# MicroMouse_v04.net
KiCad netlist of a schematic drawn in EasyEDA Pro
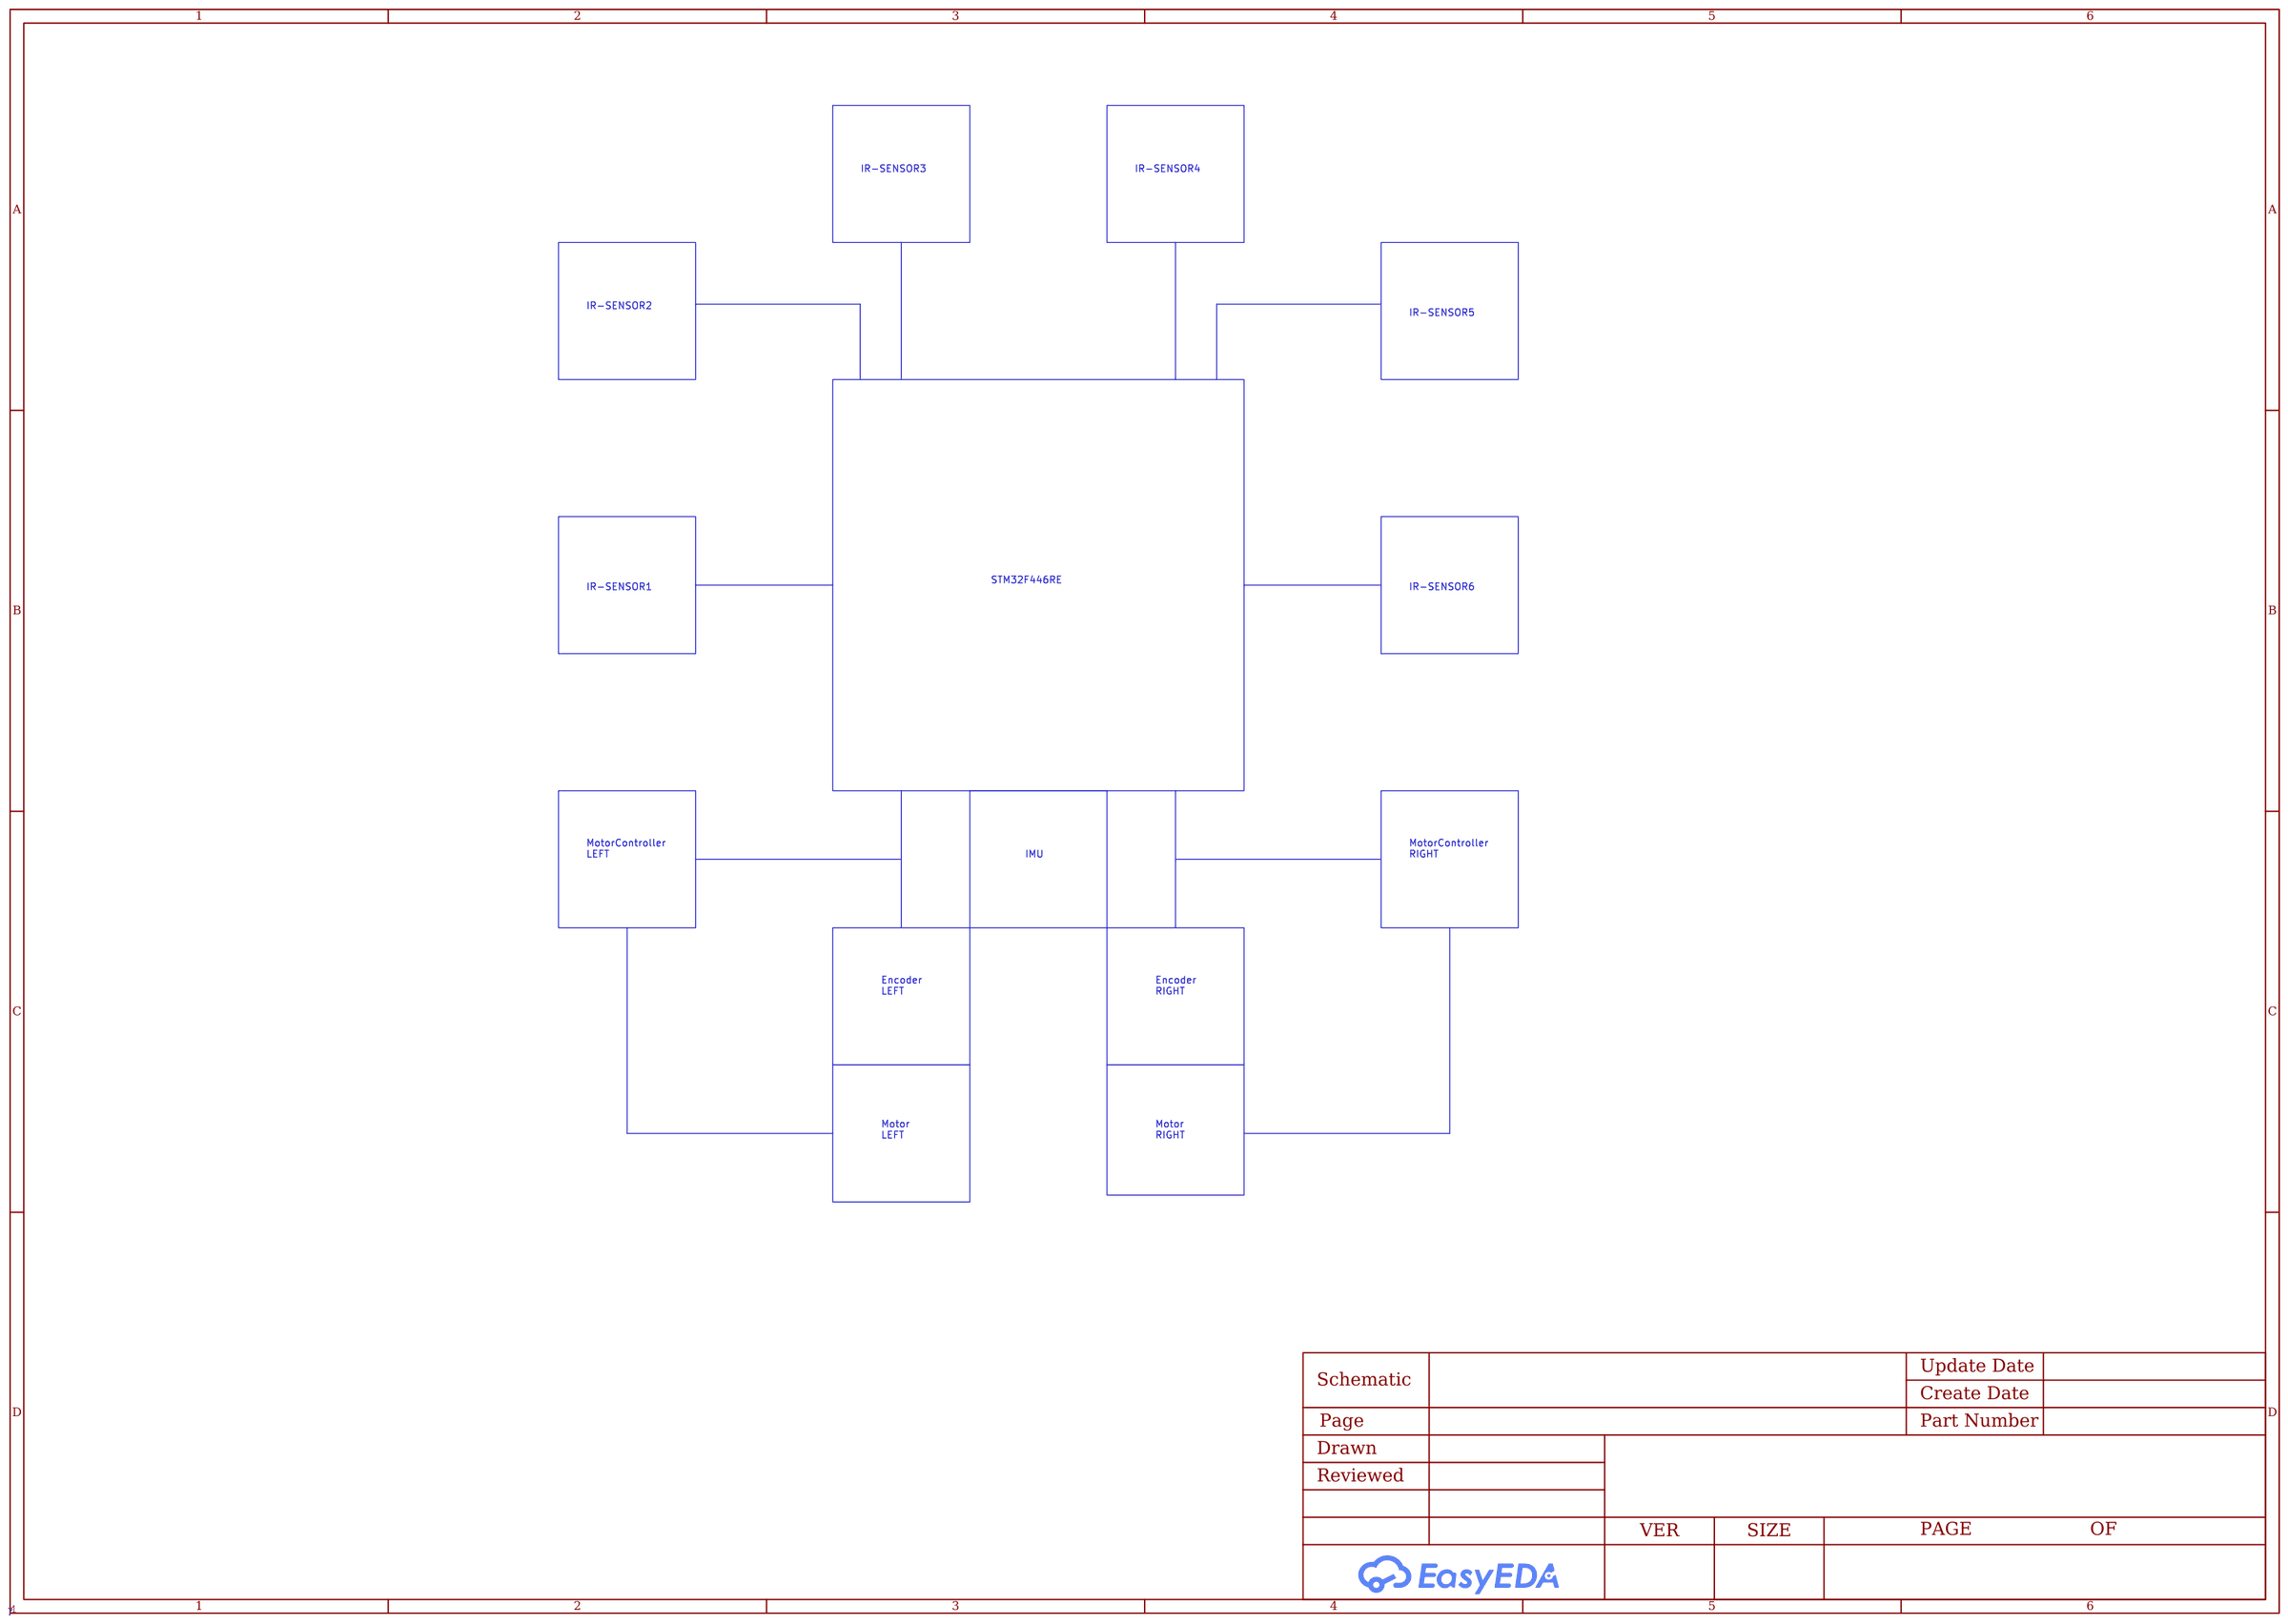
[diagram p0: Overview]
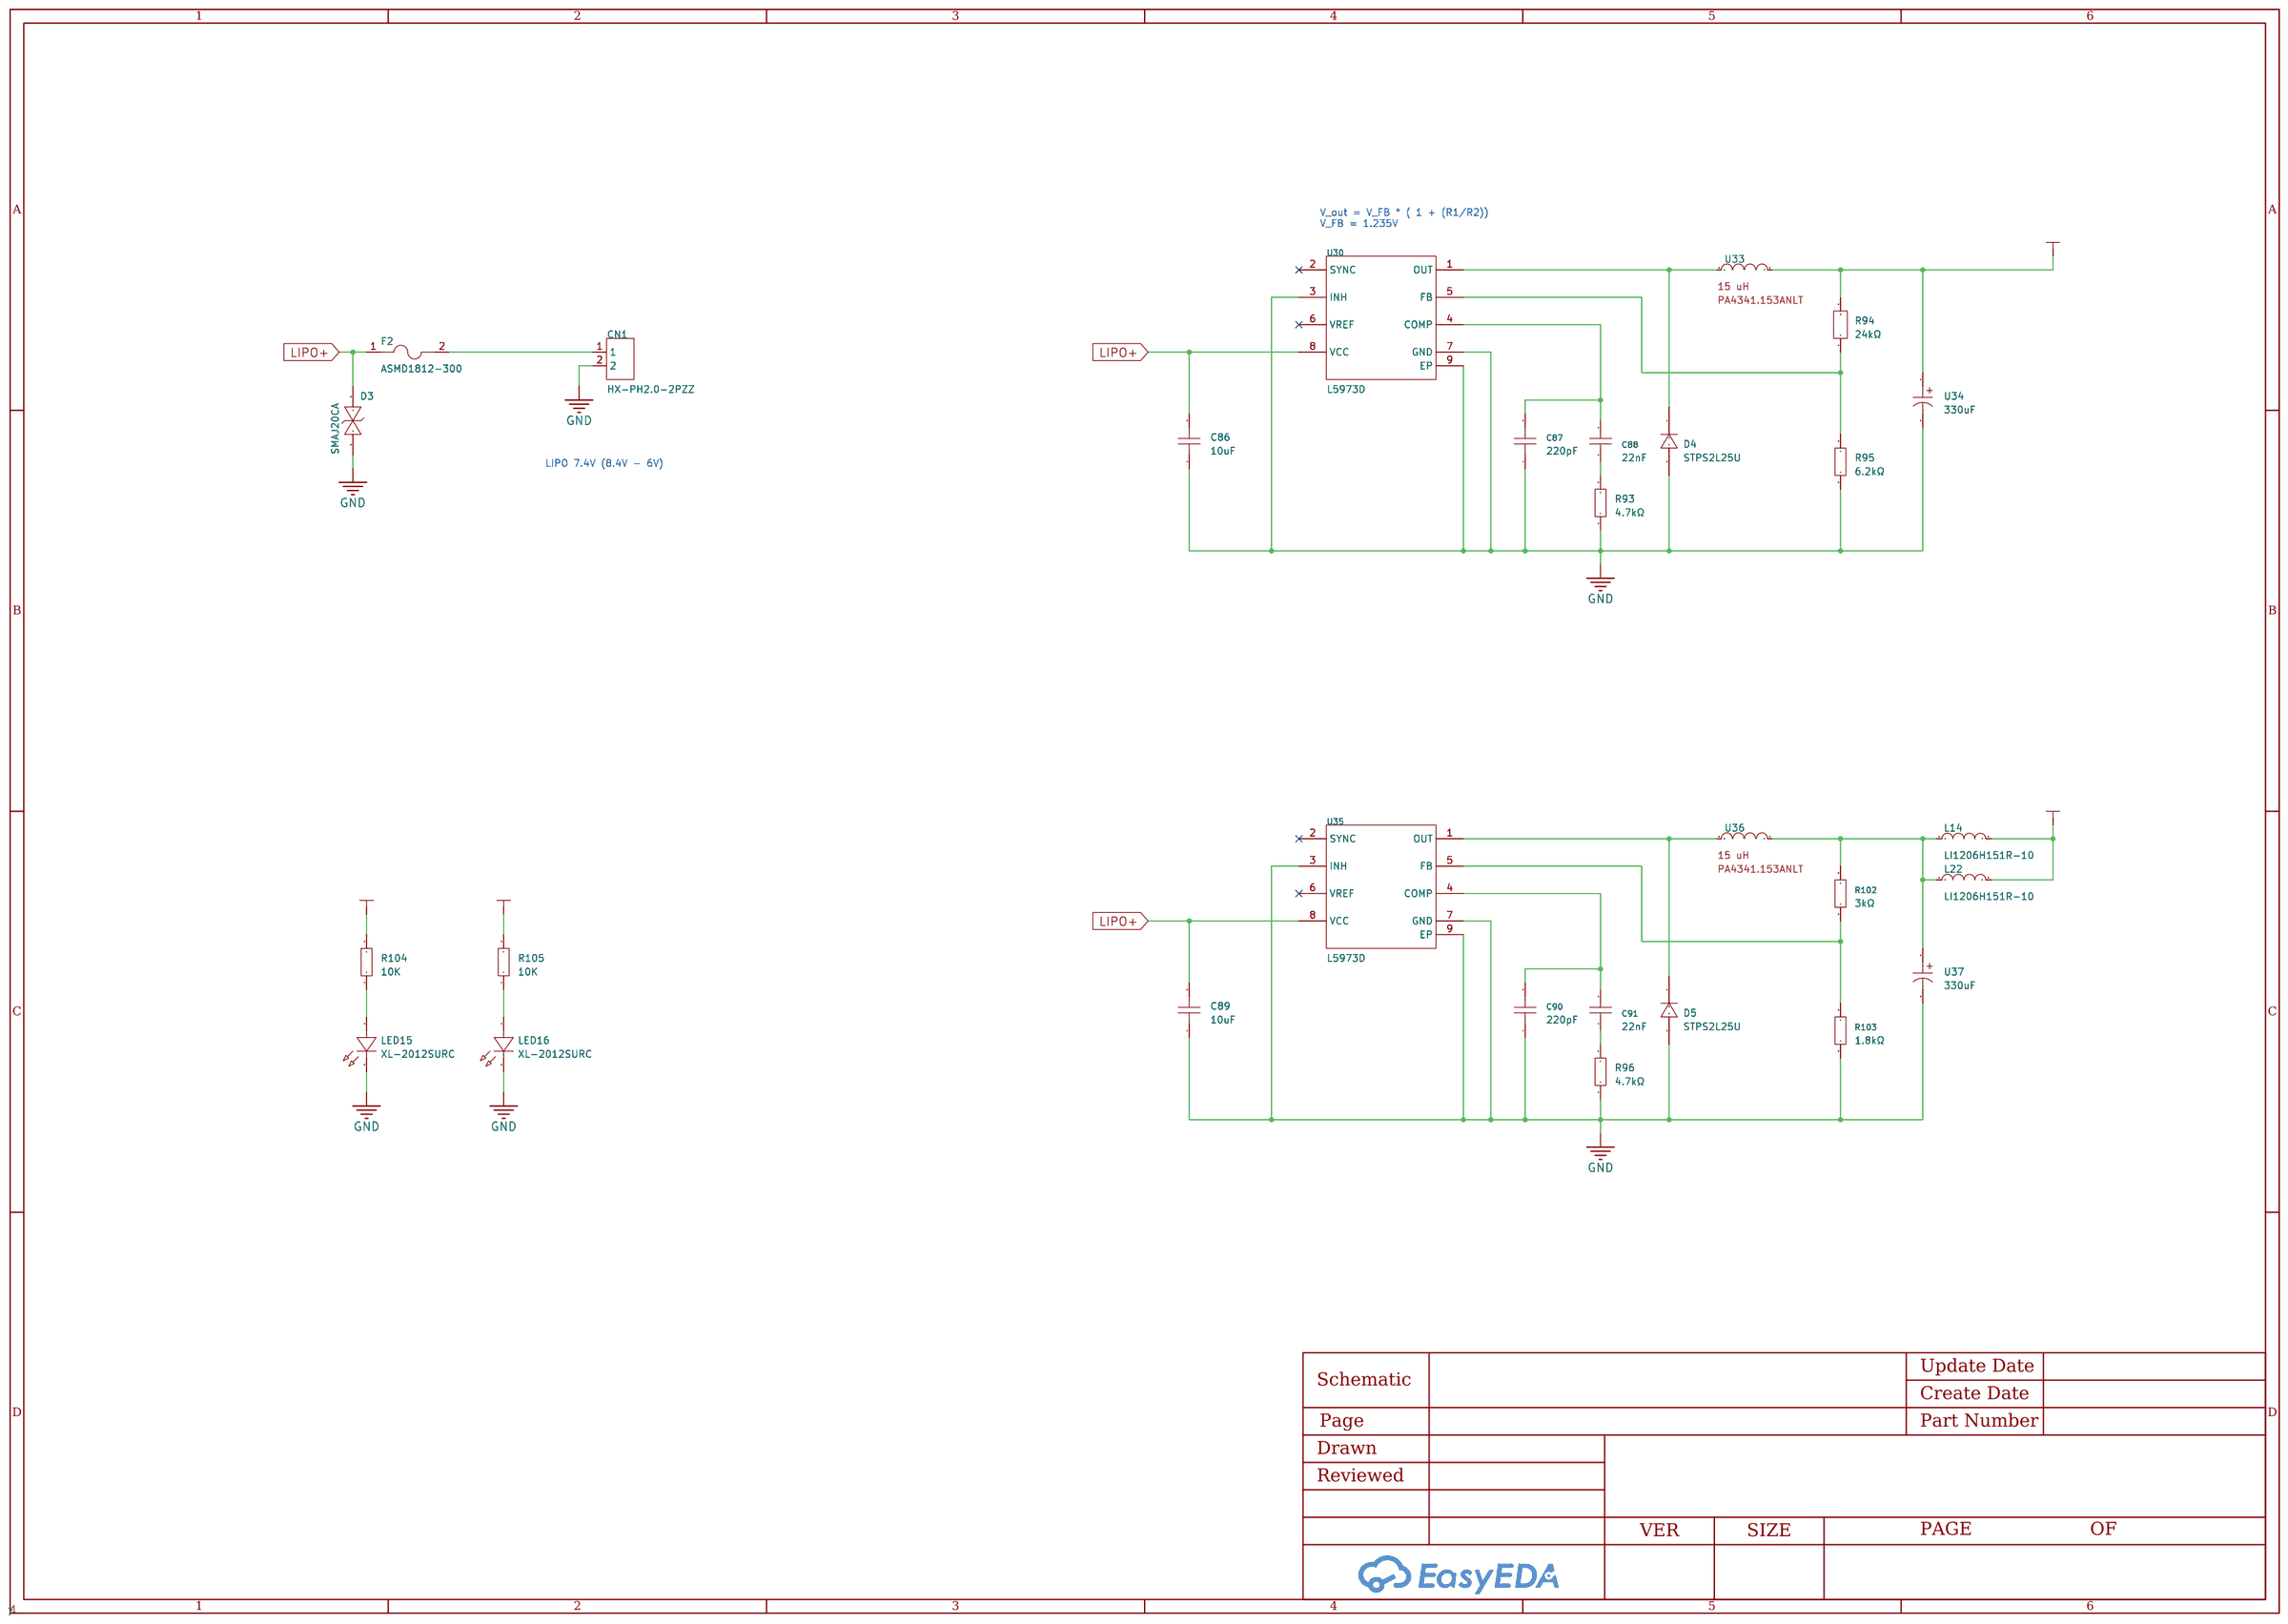
[diagram p1: VCC]
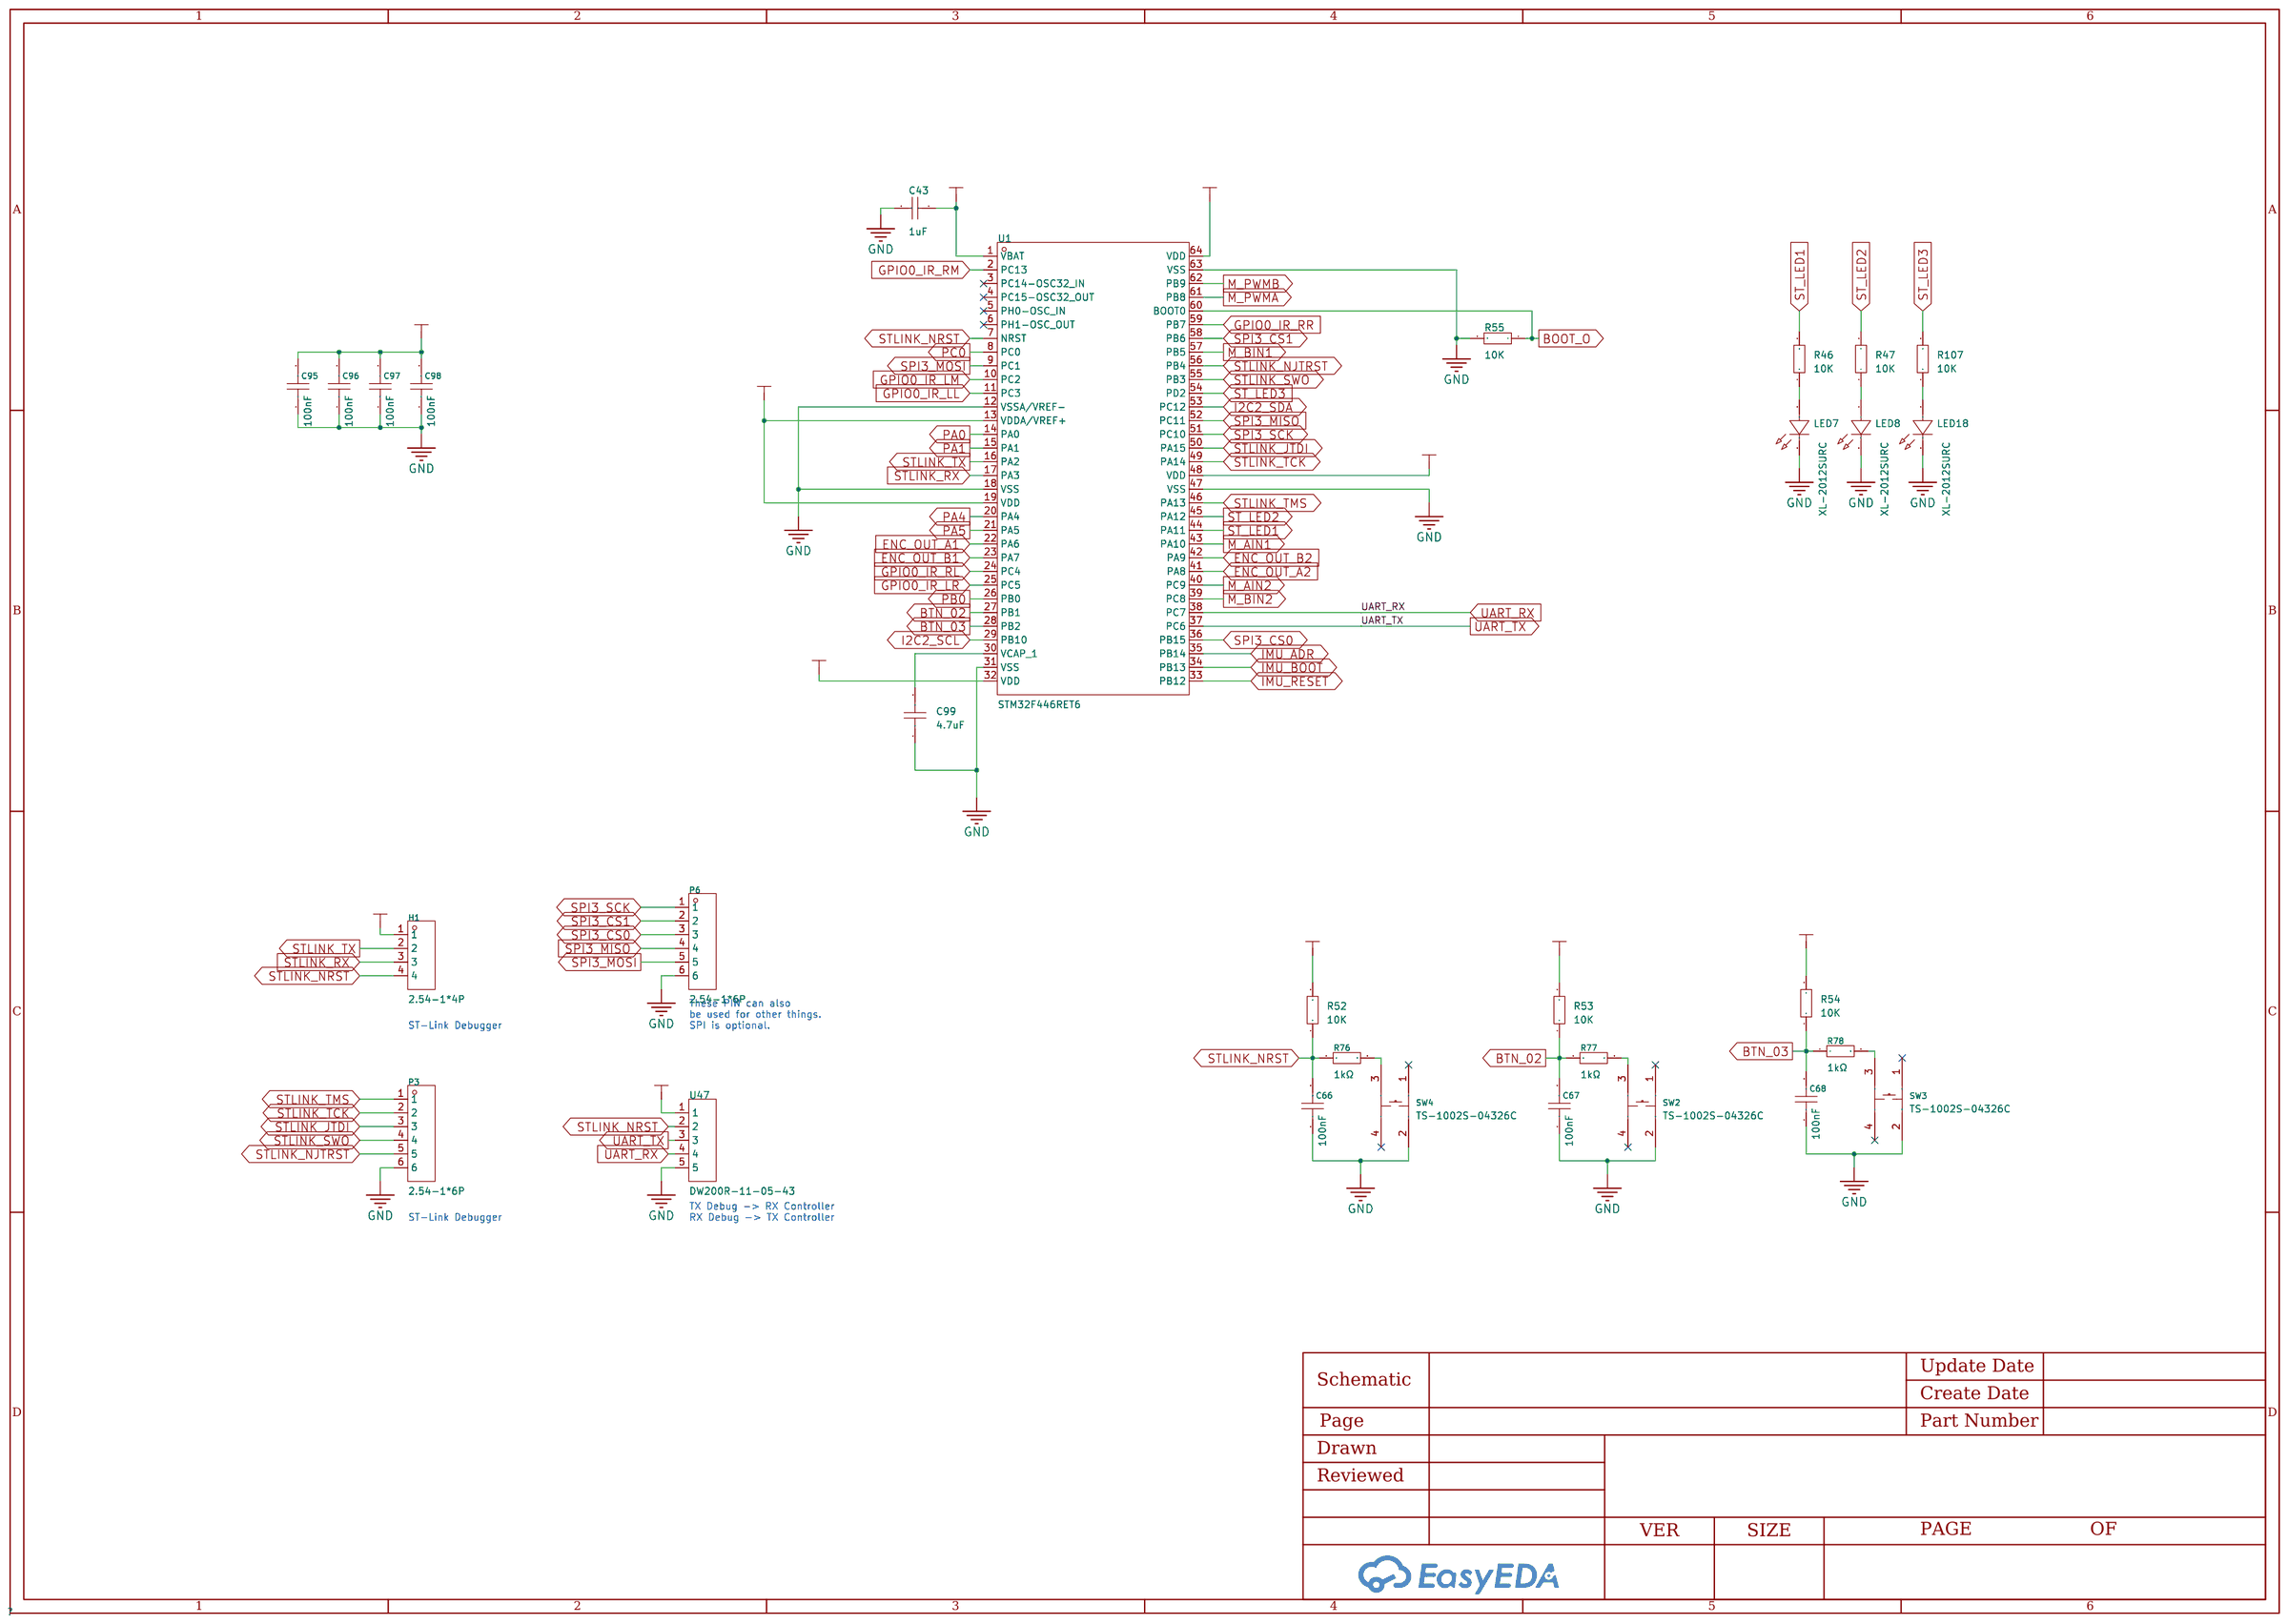
[diagram p2: Controller]
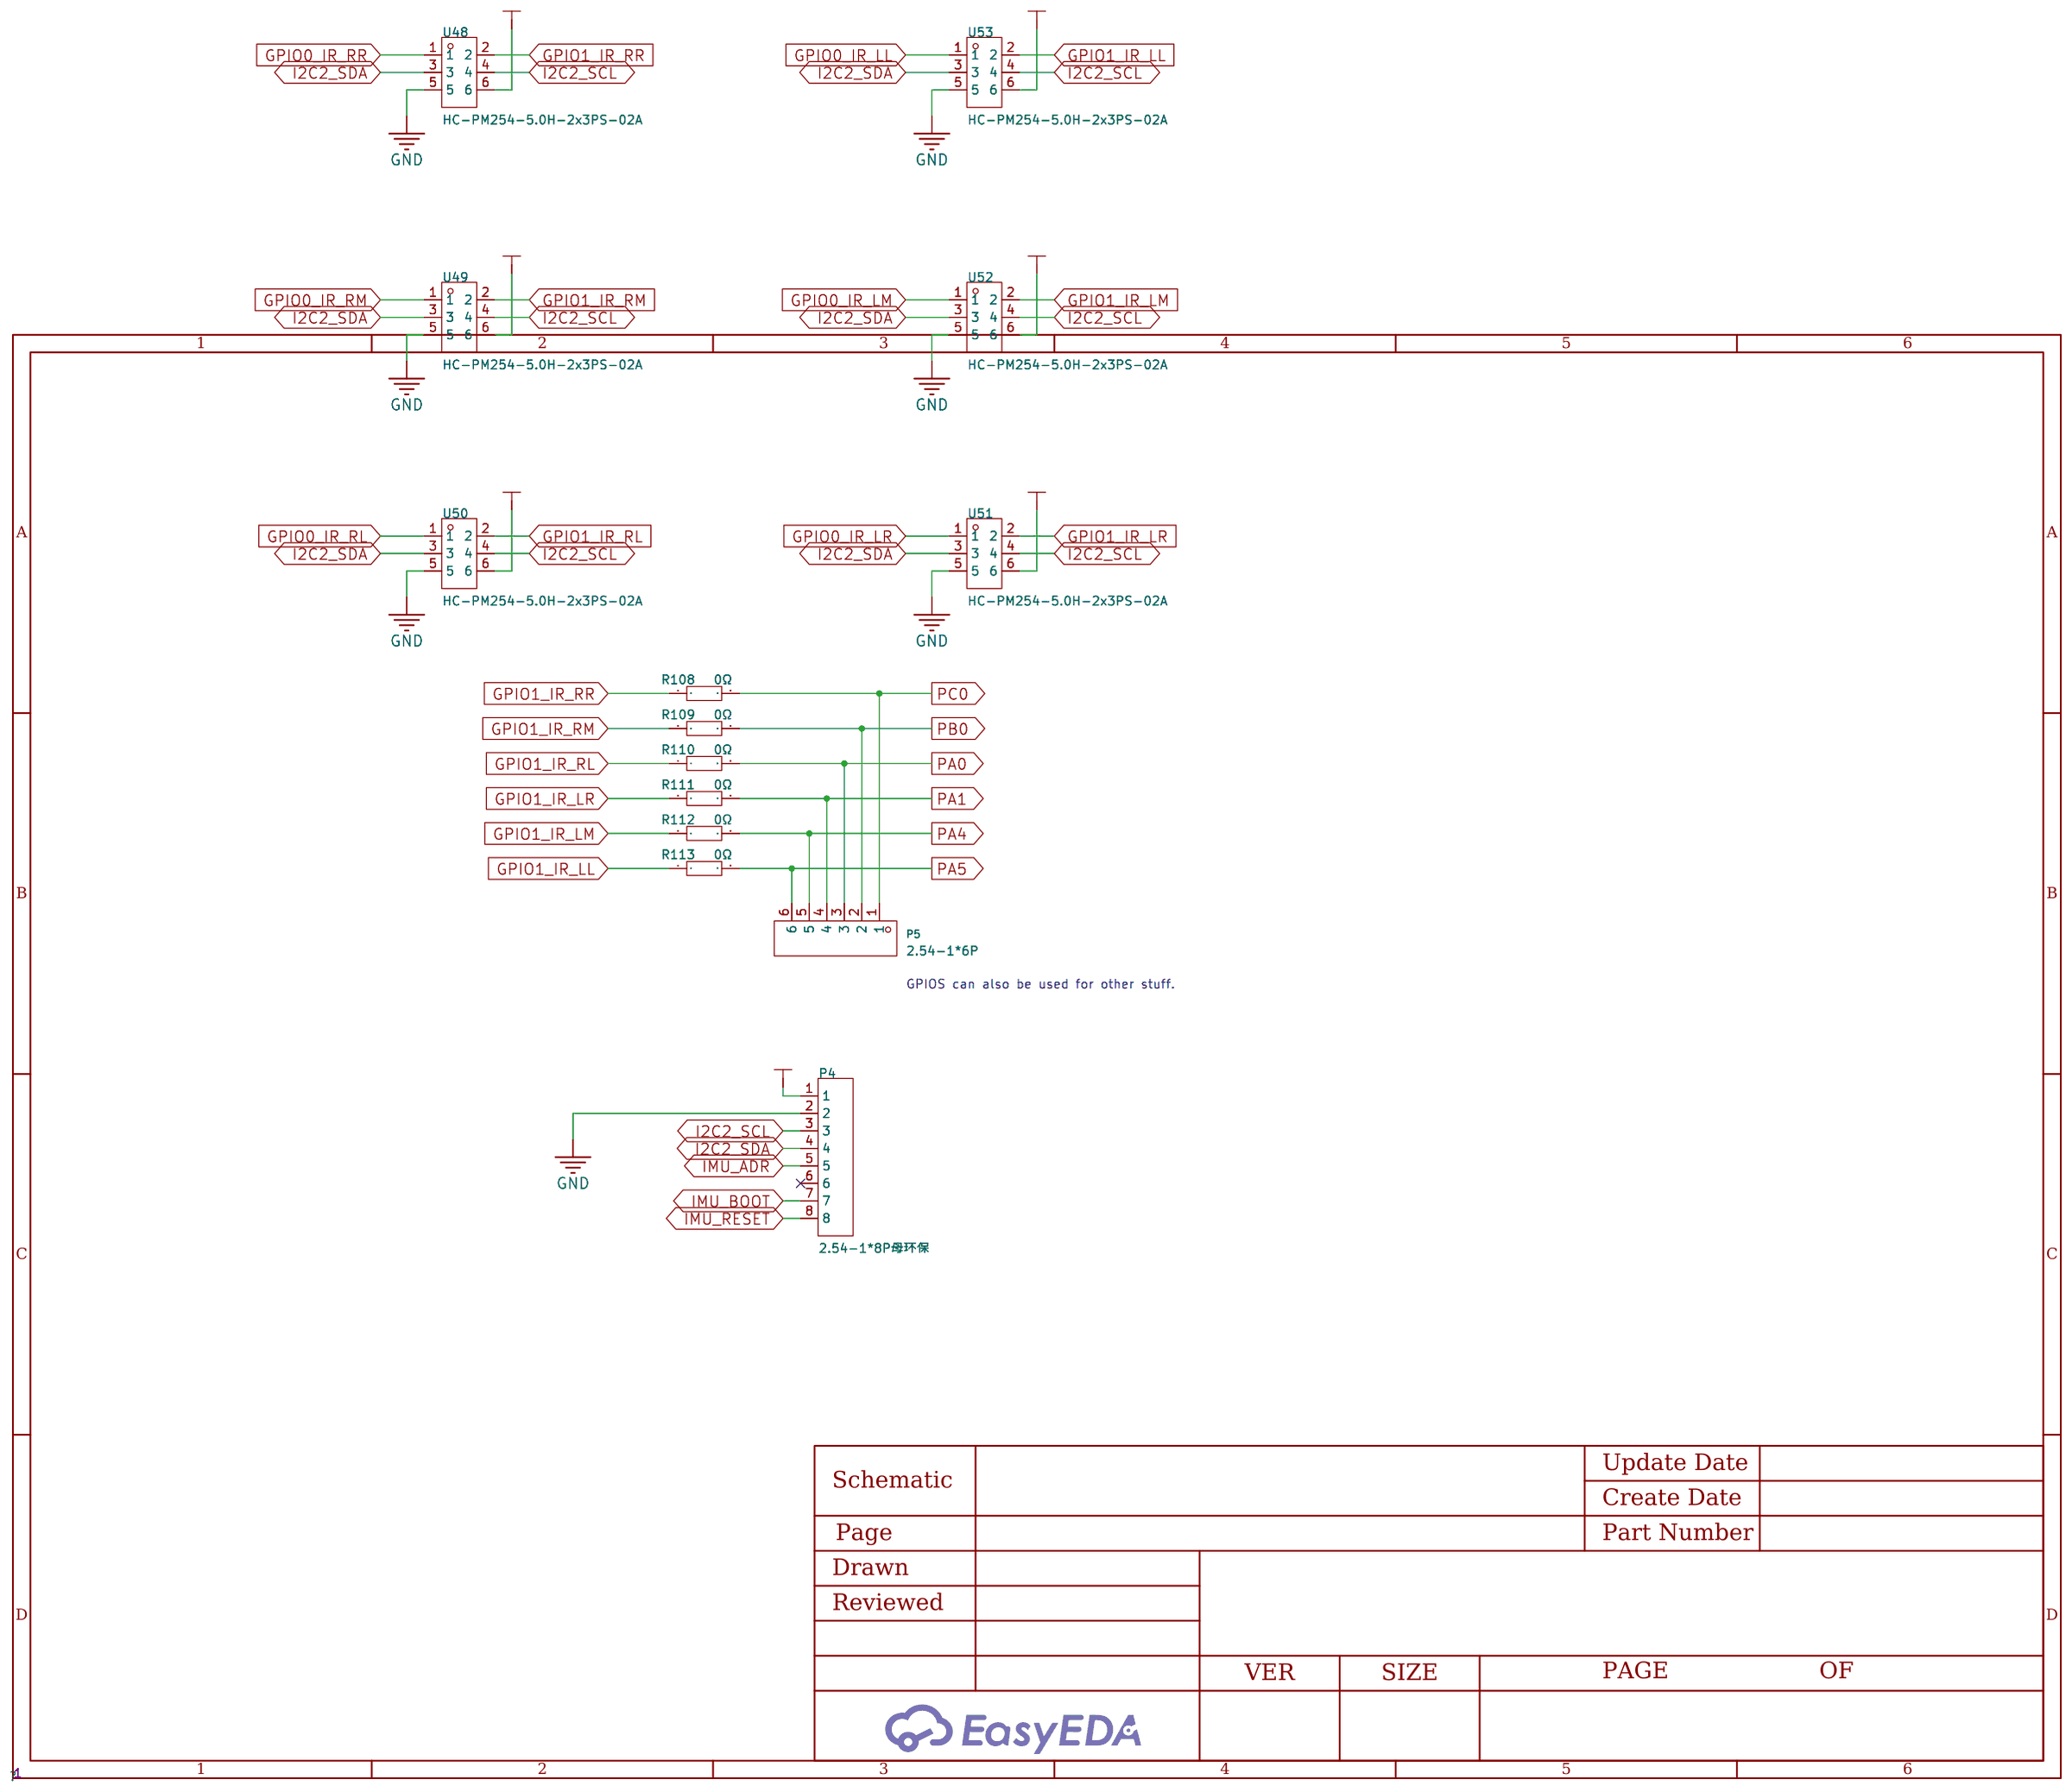
[diagram p3: Sensors]
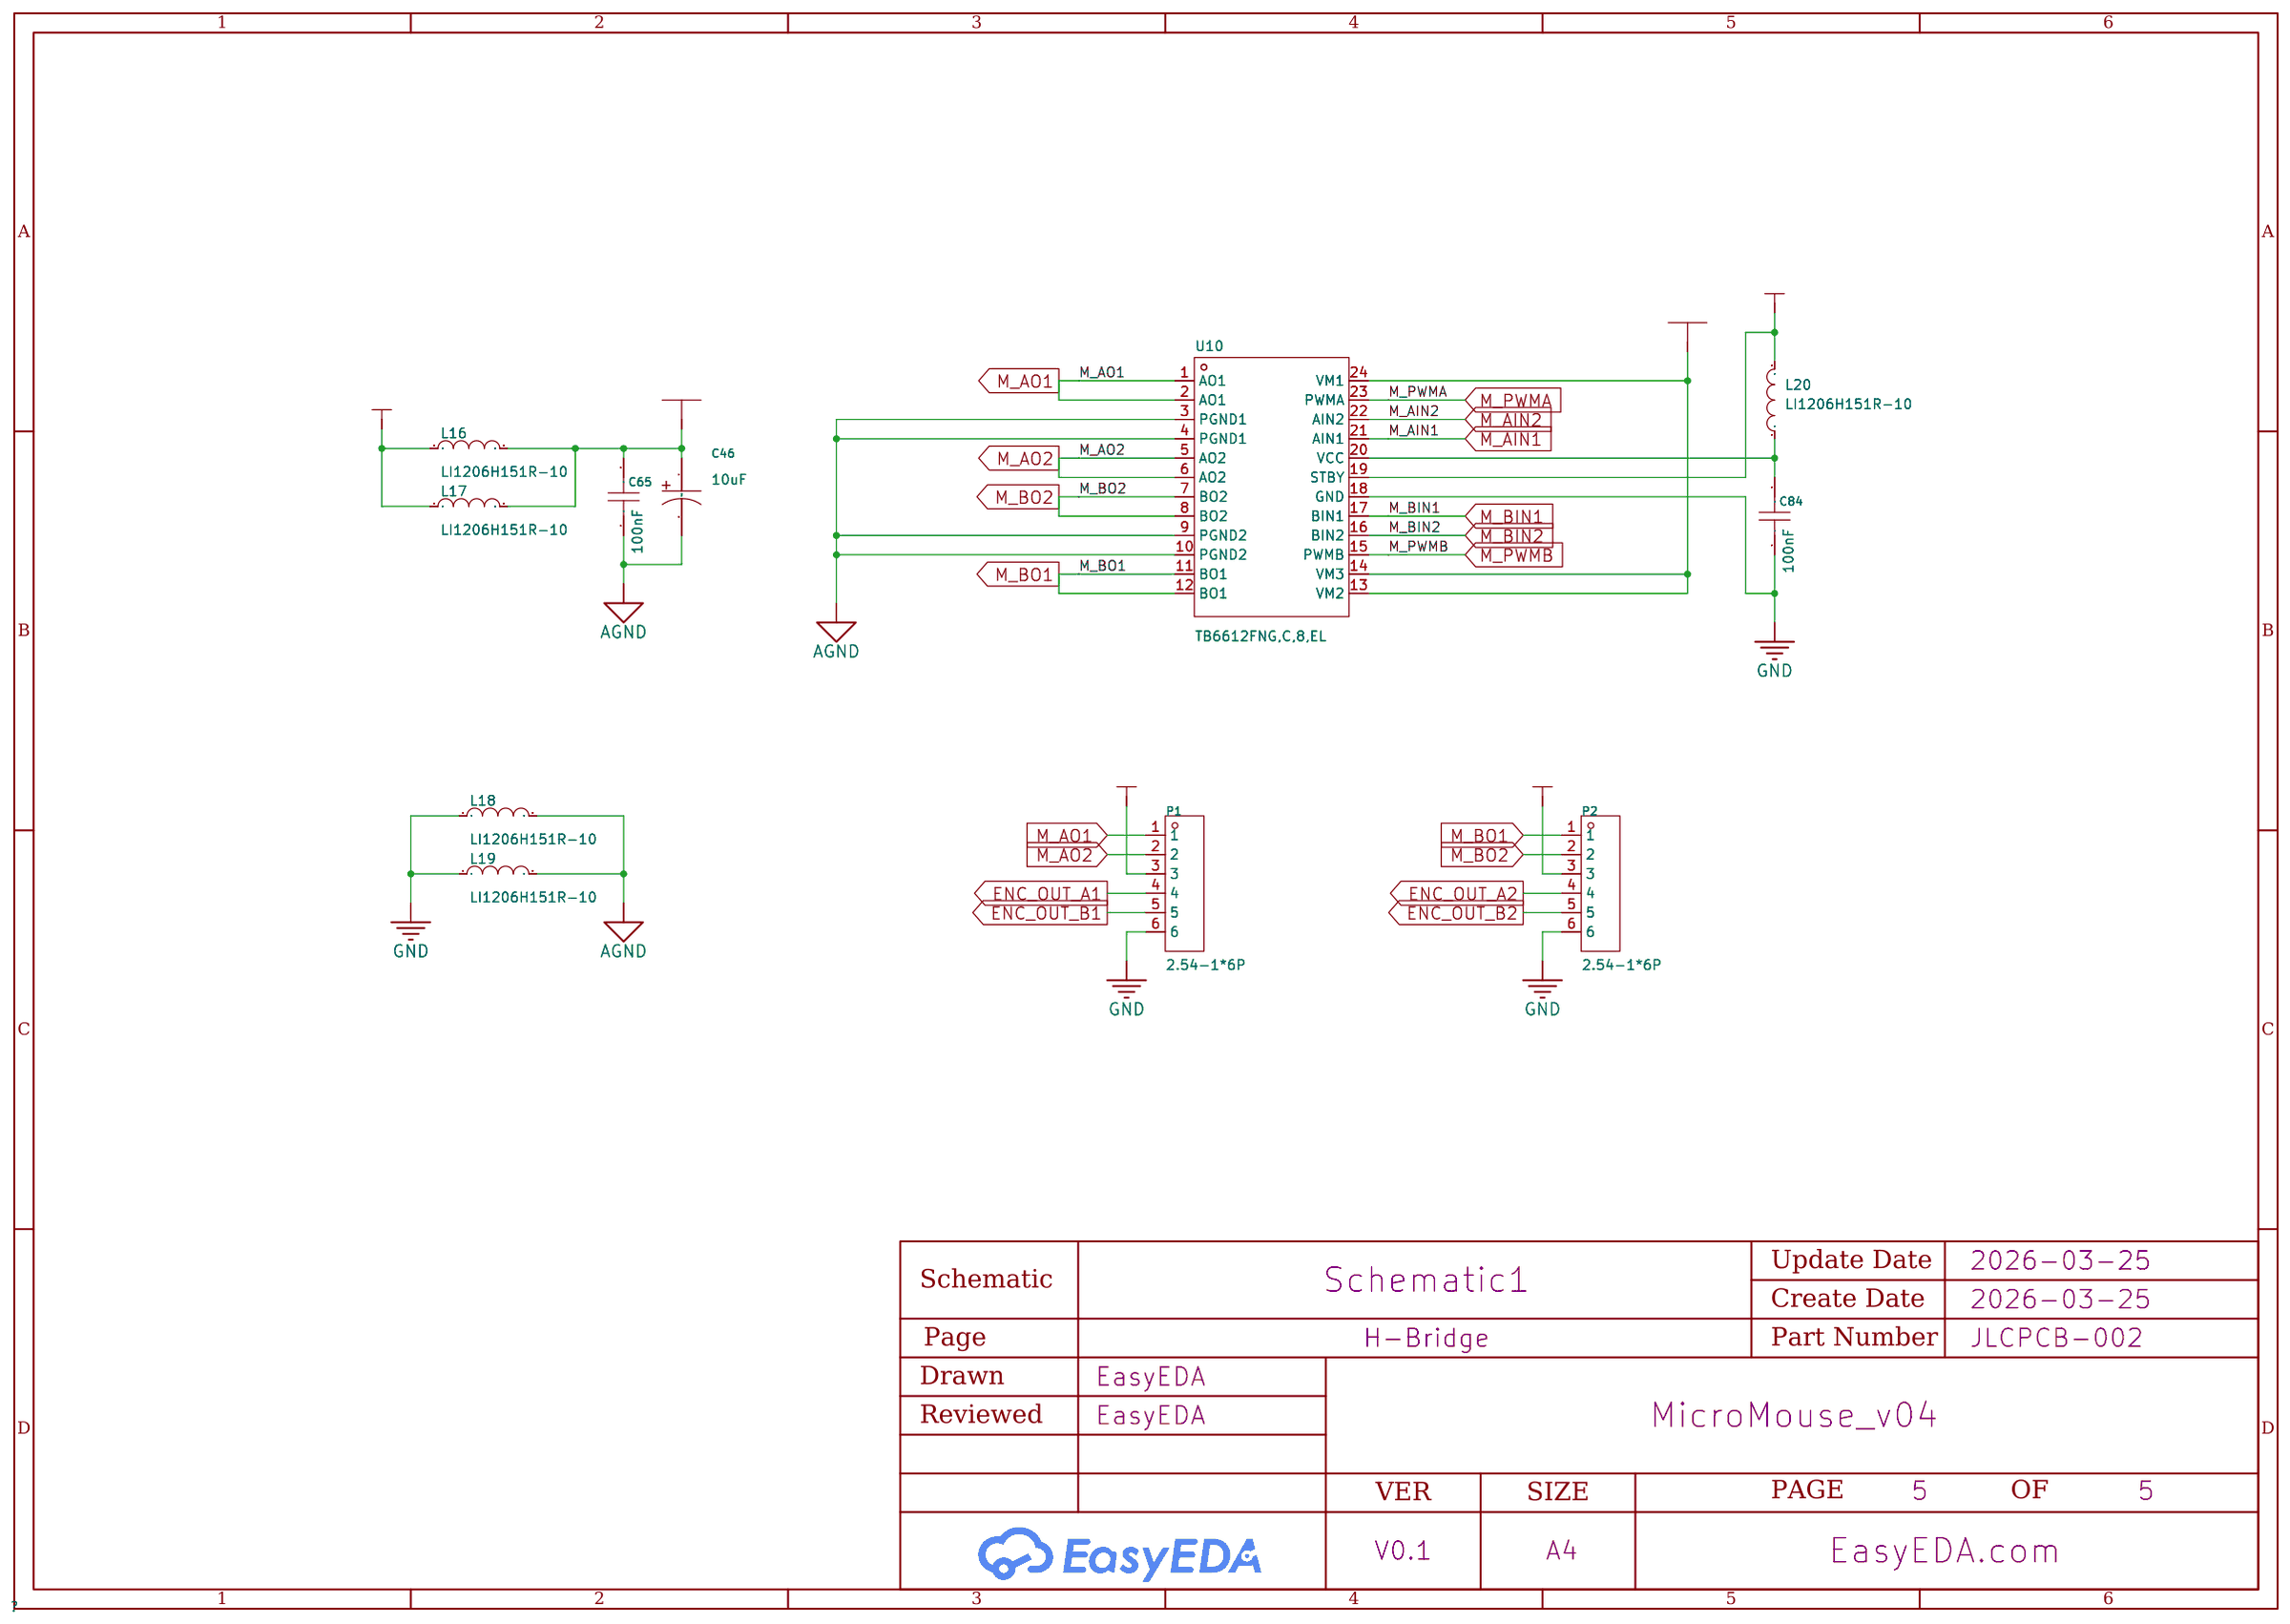
[diagram p4: H-Bridge Mot]
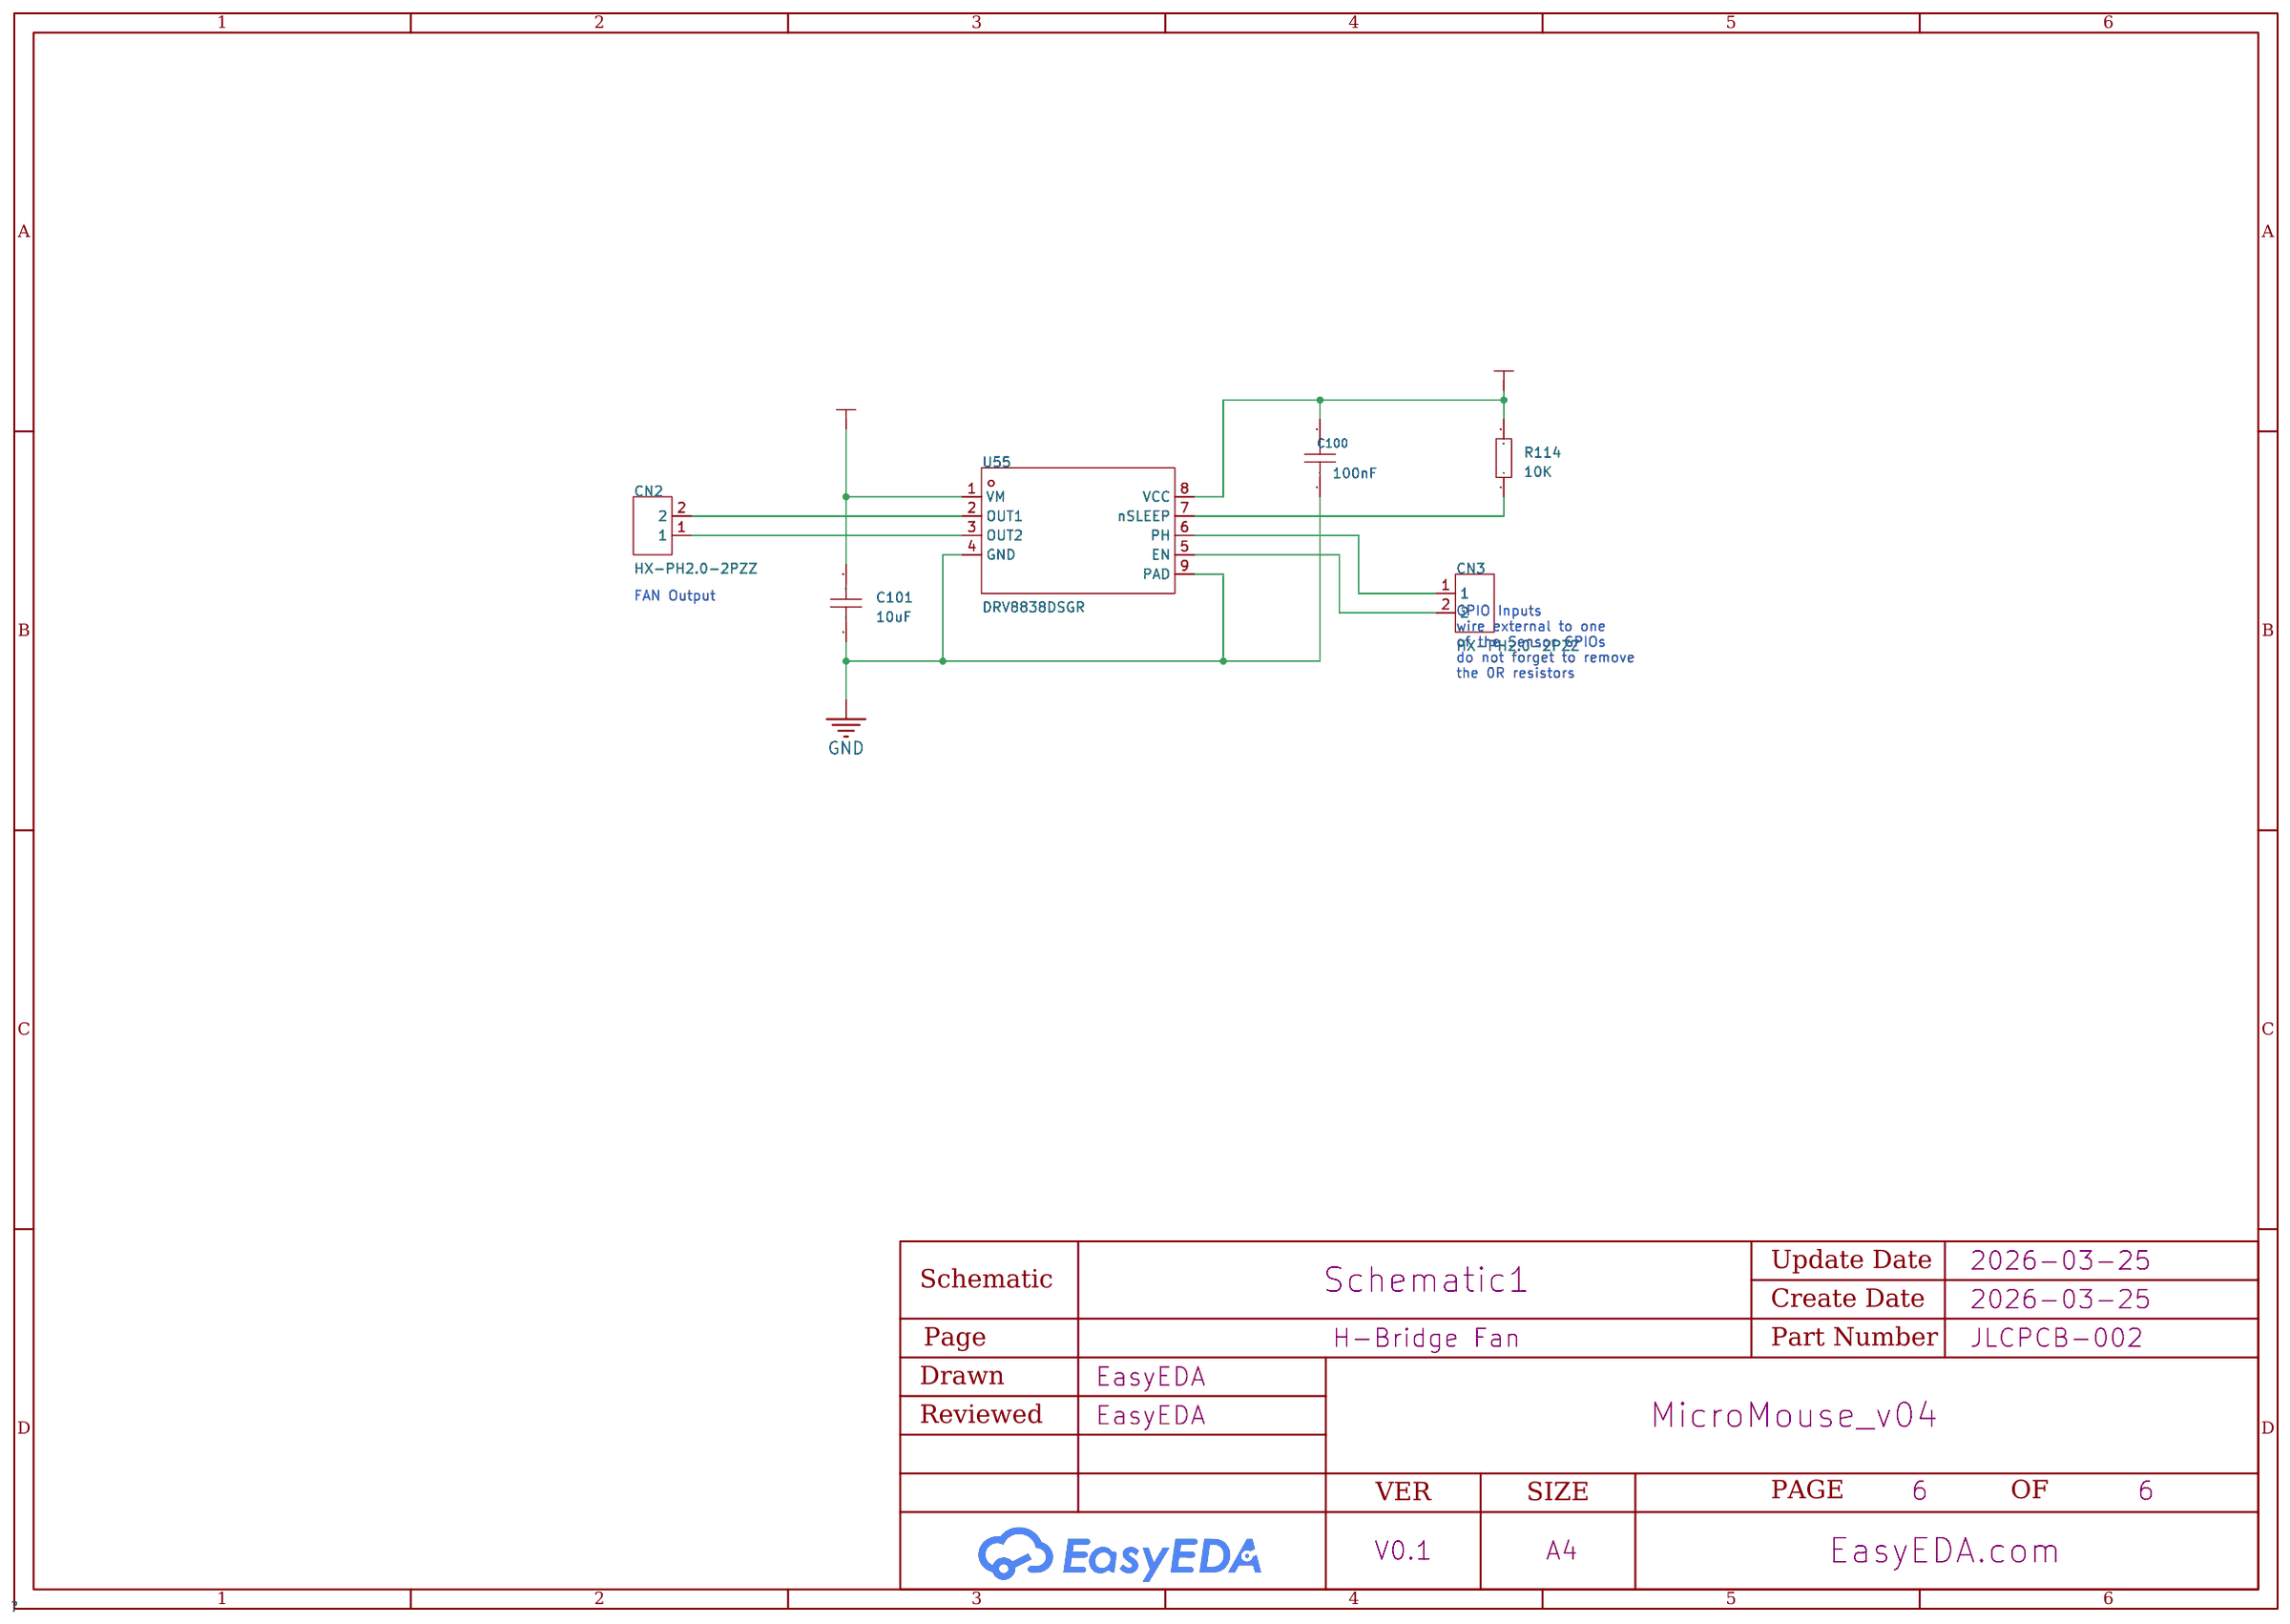
[diagram p5: H-Bridge Fan]

(export (version "E")
  (design (tool "Eeschema 10.0.6"))
  (components
    (comp (ref "C86")
      (value "10uF")
      (footprint "easyedapro:C0805")
      (description "Capacitance:10uF Tolerance:±10% Tolerance:±10% Voltage Rating:25V Temperature Coefficient:X5R")
      (fields
        (field (name "Manufacturer Part") "CL21A106KAYNNNE")
        (field (name "Manufacturer") "SAMSUNG(三星)")
      )
      (libsource (lib "easyedapro") (part "CL21A106KAYNNNE"))
    )
    (comp (ref "C87")
      (value "220pF")
      (footprint "easyedapro:C0805")
      (description "Capacitance:22nF Tolerance:±10% Tolerance:±10% Voltage Rating:25V Temperature Coefficient:X7R")
      (fields
        (field (name "Manufacturer Part") "CC0805KRX7R8BB223")
        (field (name "Manufacturer") "YAGEO(国巨)")
      )
      (libsource (lib "easyedapro") (part "CC0805KRX7R8BB223"))
    )
    (comp (ref "C88")
      (value "22nF")
      (footprint "easyedapro:C0805")
      (description "Capacitance:220pF Tolerance:±10% Tolerance:±10% Voltage Rating:50V Temperature Coefficient:X7R")
      (fields
        (field (name "Manufacturer Part") "CC0805KRX7R9BB221")
        (field (name "Manufacturer") "YAGEO(国巨)")
      )
      (libsource (lib "easyedapro") (part "CC0805KRX7R9BB221"))
    )
    (comp (ref "C89")
      (value "10uF")
      (footprint "easyedapro:C0805")
      (description "Capacitance:10uF Tolerance:±10% Tolerance:±10% Voltage Rating:25V Temperature Coefficient:X5R")
      (fields
        (field (name "Manufacturer Part") "CL21A106KAYNNNE")
        (field (name "Manufacturer") "SAMSUNG(三星)")
      )
      (libsource (lib "easyedapro") (part "CL21A106KAYNNNE"))
    )
    (comp (ref "C90")
      (value "220pF")
      (footprint "easyedapro:C0805")
      (description "Capacitance:22nF Tolerance:±10% Tolerance:±10% Voltage Rating:25V Temperature Coefficient:X7R")
      (fields
        (field (name "Manufacturer Part") "CC0805KRX7R8BB223")
        (field (name "Manufacturer") "YAGEO(国巨)")
      )
      (libsource (lib "easyedapro") (part "CC0805KRX7R8BB223"))
    )
    (comp (ref "C91")
      (value "22nF")
      (footprint "easyedapro:C0805")
      (description "Capacitance:220pF Tolerance:±10% Tolerance:±10% Voltage Rating:50V Temperature Coefficient:X7R")
      (fields
        (field (name "Manufacturer Part") "CC0805KRX7R9BB221")
        (field (name "Manufacturer") "YAGEO(国巨)")
      )
      (libsource (lib "easyedapro") (part "CC0805KRX7R9BB221"))
    )
    (comp (ref "CN1")
      (value "HX-PH2.0-2PZZ")
      (footprint "easyedapro:CONN-TH_2P-P2.50_HX-PH2.0-2PZZ")
      (fields (field (name "Manufacturer") "hanxia(韩下)"))
      (libsource (lib "easyedapro") (part "HX-PH2.0-2PZZ"))
    )
    (comp (ref "D3")
      (value "SMAJ20CA")
      (footprint "easyedapro:SMA_L4.3-W2.6-LS5.2-BI")
      (fields (field (name "Manufacturer") "High Diode(海德)"))
      (libsource (lib "easyedapro") (part "SMAJ20CA_C514090"))
    )
    (comp (ref "D4")
      (value "STPS2L25U")
      (footprint "easyedapro:SMB_L4.6-W3.6-LS5.3-RD")
      (fields (field (name "Manufacturer") "ST(意法半导体)"))
      (libsource (lib "easyedapro") (part "STPS2L25U"))
    )
    (comp (ref "D5")
      (value "STPS2L25U")
      (footprint "easyedapro:SMB_L4.6-W3.6-LS5.3-RD")
      (fields (field (name "Manufacturer") "ST(意法半导体)"))
      (libsource (lib "easyedapro") (part "STPS2L25U"))
    )
    (comp (ref "F2")
      (value "ASMD1812-300")
      (footprint "easyedapro:F1812")
      (fields (field (name "Manufacturer") "JDTfuse(集电通)"))
      (libsource (lib "easyedapro") (part "ASMD1812-300"))
    )
    (comp (ref "L14")
      (value "LI1206H151R-10")
      (footprint "easyedapro:L1206")
      (description "Impedance @ Frequency:150Ω@100MHz DC Resistance(DCR):150mΩ Number of Circuits:1")
      (fields (field (name "Manufacturer") "Laird(莱尔德)"))
      (libsource (lib "easyedapro") (part "LI1206H151R-10"))
    )
    (comp (ref "L22")
      (value "LI1206H151R-10")
      (footprint "easyedapro:L1206")
      (description "Impedance @ Frequency:150Ω@100MHz DC Resistance(DCR):150mΩ Number of Circuits:1")
      (fields (field (name "Manufacturer") "Laird(莱尔德)"))
      (libsource (lib "easyedapro") (part "LI1206H151R-10"))
    )
    (comp (ref "LED15")
      (value "XL-2012SURC")
      (footprint "easyedapro:LED0805-R-RD")
      (fields (field (name "Manufacturer") "XINGLIGHT(成兴光)"))
      (libsource (lib "easyedapro") (part "XL-2012SURC"))
    )
    (comp (ref "LED16")
      (value "XL-2012SURC")
      (footprint "easyedapro:LED0805-R-RD")
      (fields (field (name "Manufacturer") "XINGLIGHT(成兴光)"))
      (libsource (lib "easyedapro") (part "XL-2012SURC"))
    )
    (comp (ref "R93")
      (value "4.7kΩ")
      (footprint "easyedapro:R0603")
      (fields
        (field (name "Manufacturer Part") "0603WAF4701T5E")
        (field (name "Manufacturer") "UNI-ROYAL(厚声)")
      )
      (libsource (lib "easyedapro") (part "0603WAF4701T5E"))
    )
    (comp (ref "R94")
      (value "24kΩ")
      (footprint "easyedapro:R0603")
      (fields (field (name "Manufacturer Part") "FRC0603F2402TS") (field (name "Manufacturer") "FOJAN(富捷)"))
      (libsource (lib "easyedapro") (part "FRC0603F2402TS"))
    )
    (comp (ref "R95")
      (value "6.2kΩ")
      (footprint "easyedapro:R0603")
      (fields
        (field (name "Manufacturer Part") "0603WAF6201T5E")
        (field (name "Manufacturer") "UNI-ROYAL(厚声)")
      )
      (libsource (lib "easyedapro") (part "0603WAF6201T5E"))
    )
    (comp (ref "R96")
      (value "4.7kΩ")
      (footprint "easyedapro:R0603")
      (fields
        (field (name "Manufacturer Part") "0603WAF4701T5E")
        (field (name "Manufacturer") "UNI-ROYAL(厚声)")
      )
      (libsource (lib "easyedapro") (part "0603WAF4701T5E"))
    )
    (comp (ref "R102")
      (value "3kΩ")
      (footprint "easyedapro:R0603")
      (fields
        (field (name "Manufacturer Part") "0603WAF3001T5E")
        (field (name "Manufacturer") "UNI-ROYAL(厚声)")
      )
      (libsource (lib "easyedapro") (part "0603WAF3001T5E"))
    )
    (comp (ref "R103")
      (value "1.8kΩ")
      (footprint "easyedapro:R0603")
      (fields
        (field (name "Manufacturer Part") "0603WAF1801T5E")
        (field (name "Manufacturer") "UNI-ROYAL(厚声)")
      )
      (libsource (lib "easyedapro") (part "0603WAF1801T5E"))
    )
    (comp (ref "R104")
      (value "10K")
      (footprint "easyedapro:R0402")
      (description "DNI")
      (libsource (lib "easyedapro") (part "Res"))
    )
    (comp (ref "R105")
      (value "10K")
      (footprint "easyedapro:R0402")
      (description "DNI")
      (libsource (lib "easyedapro") (part "Res"))
    )
    (comp (ref "U30")
      (value "L5973D")
      (footprint "easyedapro:SOIC-8_L4.9-W3.9-P1.27-LS6.0-BL-EP")
      (fields (field (name "Manufacturer") "ST(意法半导体)"))
      (libsource (lib "easyedapro") (part "L5973D"))
    )
    (comp (ref "U33")
      (value "1.5uH")
      (footprint "easyedapro:IND-SMD_L7.6-W6.9")
      (fields
        (field (name "Manufacturer Part") "PA4341.152NLT")
        (field (name "Manufacturer") "PULSE(普思）")
        (field (name "DC Resistance (DCR)") "PA4341.153ANLT")
        (field (name "Rated Current") "15 uH")
      )
      (libsource (lib "easyedapro") (part "PA4341.152NLT"))
    )
    (comp (ref "U34")
      (value "330uF")
      (footprint "easyedapro:CAP-SMD_BD6.3-L6.6-W6.6-LS7.4-FD")
      (fields (field (name "Manufacturer Part") "RVT1A331M0607") (field (name "Manufacturer") "ROQANG(容强)"))
      (libsource (lib "easyedapro") (part "RVT1A331M0607_C7419412"))
    )
    (comp (ref "U35")
      (value "L5973D")
      (footprint "easyedapro:SOIC-8_L4.9-W3.9-P1.27-LS6.0-BL-EP")
      (fields (field (name "Manufacturer") "ST(意法半导体)"))
      (libsource (lib "easyedapro") (part "L5973D"))
    )
    (comp (ref "U36")
      (value "1.5uH")
      (footprint "easyedapro:IND-SMD_L7.6-W6.9")
      (fields
        (field (name "Manufacturer Part") "PA4341.152NLT")
        (field (name "Manufacturer") "PULSE(普思）")
        (field (name "DC Resistance (DCR)") "PA4341.153ANLT")
        (field (name "Rated Current") "15 uH")
      )
      (libsource (lib "easyedapro") (part "PA4341.152NLT"))
    )
    (comp (ref "U37")
      (value "330uF")
      (footprint "easyedapro:CAP-SMD_BD6.3-L6.6-W6.6-LS7.4-FD")
      (fields (field (name "Manufacturer Part") "RVT1A331M0607") (field (name "Manufacturer") "ROQANG(容强)"))
      (libsource (lib "easyedapro") (part "RVT1A331M0607_C7419412"))
    )
    (comp (ref "C43")
      (value "1uF")
      (footprint "easyedapro:C0603")
      (fields
        (field (name "Manufacturer Part") "CL10A105KO8NNNC")
        (field (name "Manufacturer") "SAMSUNG(三星)")
      )
      (libsource (lib "easyedapro") (part "CL10A105KO8NNNC"))
    )
    (comp (ref "C66")
      (value "100nF")
      (footprint "easyedapro:C0603")
      (fields
        (field (name "Manufacturer Part") "CC0603KRX7R6BB104")
        (field (name "Manufacturer") "YAGEO(国巨)")
      )
      (libsource (lib "easyedapro") (part "CC0603KRX7R6BB104"))
    )
    (comp (ref "C67")
      (value "100nF")
      (footprint "easyedapro:C0603")
      (fields
        (field (name "Manufacturer Part") "CC0603KRX7R6BB104")
        (field (name "Manufacturer") "YAGEO(国巨)")
      )
      (libsource (lib "easyedapro") (part "CC0603KRX7R6BB104"))
    )
    (comp (ref "C68")
      (value "100nF")
      (footprint "easyedapro:C0603")
      (fields
        (field (name "Manufacturer Part") "CC0603KRX7R6BB104")
        (field (name "Manufacturer") "YAGEO(国巨)")
      )
      (libsource (lib "easyedapro") (part "CC0603KRX7R6BB104"))
    )
    (comp (ref "C95")
      (value "100nF")
      (footprint "easyedapro:C0603")
      (fields
        (field (name "Manufacturer Part") "CC0603KRX7R6BB104")
        (field (name "Manufacturer") "YAGEO(国巨)")
      )
      (libsource (lib "easyedapro") (part "CC0603KRX7R6BB104"))
    )
    (comp (ref "C96")
      (value "100nF")
      (footprint "easyedapro:C0603")
      (fields
        (field (name "Manufacturer Part") "CC0603KRX7R6BB104")
        (field (name "Manufacturer") "YAGEO(国巨)")
      )
      (libsource (lib "easyedapro") (part "CC0603KRX7R6BB104"))
    )
    (comp (ref "C97")
      (value "100nF")
      (footprint "easyedapro:C0603")
      (fields
        (field (name "Manufacturer Part") "CC0603KRX7R6BB104")
        (field (name "Manufacturer") "YAGEO(国巨)")
      )
      (libsource (lib "easyedapro") (part "CC0603KRX7R6BB104"))
    )
    (comp (ref "C98")
      (value "100nF")
      (footprint "easyedapro:C0603")
      (fields
        (field (name "Manufacturer Part") "CC0603KRX7R6BB104")
        (field (name "Manufacturer") "YAGEO(国巨)")
      )
      (libsource (lib "easyedapro") (part "CC0603KRX7R6BB104"))
    )
    (comp (ref "C99")
      (value "4.7uF")
      (footprint "easyedapro:C0603")
      (description "Capacitance:4.7uF Tolerance:±10% Tolerance:±10% Voltage Rating:25V Temperature Coefficient:X5R")
      (fields
        (field (name "Manufacturer Part") "CGA0603X5R475K250JT")
        (field (name "Manufacturer") "HRE(芯声)")
      )
      (libsource (lib "easyedapro") (part "CGA0603X5R475K250JT"))
    )
    (comp (ref "H1")
      (value "2.54-1*4P")
      (footprint "easyedapro:HDR-TH_4P-P2.54-V-F")
      (fields (field (name "Manufacturer") "BOOMELE(博穆精密)"))
      (libsource (lib "easyedapro") (part "2.54-1*4P母"))
    )
    (comp (ref "LED7")
      (value "XL-2012SURC")
      (footprint "easyedapro:LED0805-R-RD")
      (fields (field (name "Manufacturer") "XINGLIGHT(成兴光)"))
      (libsource (lib "easyedapro") (part "XL-2012SURC"))
    )
    (comp (ref "LED8")
      (value "XL-2012SURC")
      (footprint "easyedapro:LED0805-R-RD")
      (fields (field (name "Manufacturer") "XINGLIGHT(成兴光)"))
      (libsource (lib "easyedapro") (part "XL-2012SURC"))
    )
    (comp (ref "LED18")
      (value "XL-2012SURC")
      (footprint "easyedapro:LED0805-R-RD")
      (fields (field (name "Manufacturer") "XINGLIGHT(成兴光)"))
      (libsource (lib "easyedapro") (part "XL-2012SURC"))
    )
    (comp (ref "P3")
      (value "2.54-1*6P")
      (footprint "easyedapro:HDR-TH_6P-P2.54-V-F")
      (fields (field (name "Manufacturer") "BOOMELE(博穆精密)"))
      (libsource (lib "easyedapro") (part "Header-Female-2.54_1x6"))
    )
    (comp (ref "P6")
      (value "2.54-1*6P")
      (footprint "easyedapro:HDR-TH_6P-P2.54-V-F")
      (fields (field (name "Manufacturer") "BOOMELE(博穆精密)"))
      (libsource (lib "easyedapro") (part "Header-Female-2.54_1x6"))
    )
    (comp (ref "R46")
      (value "10K")
      (footprint "easyedapro:R0402")
      (description "DNI")
      (libsource (lib "easyedapro") (part "Res"))
    )
    (comp (ref "R47")
      (value "10K")
      (footprint "easyedapro:R0402")
      (description "DNI")
      (libsource (lib "easyedapro") (part "Res"))
    )
    (comp (ref "R52")
      (value "10K")
      (footprint "easyedapro:R0402")
      (description "DNI")
      (libsource (lib "easyedapro") (part "Res"))
    )
    (comp (ref "R53")
      (value "10K")
      (footprint "easyedapro:R0402")
      (description "DNI")
      (libsource (lib "easyedapro") (part "Res"))
    )
    (comp (ref "R54")
      (value "10K")
      (footprint "easyedapro:R0402")
      (description "DNI")
      (libsource (lib "easyedapro") (part "Res"))
    )
    (comp (ref "R55")
      (value "10K")
      (footprint "easyedapro:R0402")
      (description "DNI")
      (libsource (lib "easyedapro") (part "Res"))
    )
    (comp (ref "R76")
      (value "1kΩ")
      (footprint "easyedapro:R0603")
      (fields
        (field (name "Manufacturer Part") "0603WAF1001T5E")
        (field (name "Manufacturer") "UNI-ROYAL(厚声)")
      )
      (libsource (lib "easyedapro") (part "0603WAF1001T5E"))
    )
    (comp (ref "R77")
      (value "1kΩ")
      (footprint "easyedapro:R0603")
      (fields
        (field (name "Manufacturer Part") "0603WAF1001T5E")
        (field (name "Manufacturer") "UNI-ROYAL(厚声)")
      )
      (libsource (lib "easyedapro") (part "0603WAF1001T5E"))
    )
    (comp (ref "R78")
      (value "1kΩ")
      (footprint "easyedapro:R0603")
      (fields
        (field (name "Manufacturer Part") "0603WAF1001T5E")
        (field (name "Manufacturer") "UNI-ROYAL(厚声)")
      )
      (libsource (lib "easyedapro") (part "0603WAF1001T5E"))
    )
    (comp (ref "R107")
      (value "10K")
      (footprint "easyedapro:R0402")
      (description "DNI")
      (libsource (lib "easyedapro") (part "Res"))
    )
    (comp (ref "SW2")
      (value "TS-1002S-04326C")
      (footprint "easyedapro:KEY-SMD_4P-L6.0-W6.0-P4.50-LS9.0")
      (fields (field (name "Manufacturer") "XUNPU(讯普)"))
      (libsource (lib "easyedapro") (part "TS-1002S-04326C"))
    )
    (comp (ref "SW3")
      (value "TS-1002S-04326C")
      (footprint "easyedapro:KEY-SMD_4P-L6.0-W6.0-P4.50-LS9.0")
      (fields (field (name "Manufacturer") "XUNPU(讯普)"))
      (libsource (lib "easyedapro") (part "TS-1002S-04326C"))
    )
    (comp (ref "SW4")
      (value "TS-1002S-04326C")
      (footprint "easyedapro:KEY-SMD_4P-L6.0-W6.0-P4.50-LS9.0")
      (fields (field (name "Manufacturer") "XUNPU(讯普)"))
      (libsource (lib "easyedapro") (part "TS-1002S-04326C"))
    )
    (comp (ref "U1")
      (value "STM32F446RET6")
      (footprint "easyedapro:LQFP-64_L10.0-W10.0-P0.50-LS12.0-BL")
      (fields (field (name "Manufacturer") "ST(意法半导体)"))
      (libsource (lib "easyedapro") (part "STM32F446RET6"))
    )
    (comp (ref "U47")
      (value "DW200R-11-05-43")
      (footprint "easyedapro:HDR-TH_5P-P2.00-V-F")
      (fields (field (name "Manufacturer") "DEALON(德艺隆)"))
      (libsource (lib "easyedapro") (part "DW200R-11-05-43"))
    )
    (comp (ref "P4")
      (value "2.54-1*8P母环保")
      (footprint "easyedapro:HDR-TH_8P-P2.54-V-F_2")
      (fields (field (name "Manufacturer") "BOOMELE(博穆精密)"))
      (libsource (lib "easyedapro") (part "Header-Female-2.54_1x8"))
    )
    (comp (ref "P5")
      (value "2.54-1*6P")
      (footprint "easyedapro:HDR-TH_6P-P2.54-V-F")
      (fields (field (name "Manufacturer") "BOOMELE(博穆精密)"))
      (libsource (lib "easyedapro") (part "Header-Female-2.54_1x6"))
    )
    (comp (ref "R108")
      (value "0Ω")
      (footprint "easyedapro:R0603")
      (fields
        (field (name "Manufacturer Part") "0603WAF0000T5E")
        (field (name "Manufacturer") "UNI-ROYAL(厚声)")
      )
      (libsource (lib "easyedapro") (part "0603WAF0000T5E"))
    )
    (comp (ref "R109")
      (value "0Ω")
      (footprint "easyedapro:R0603")
      (fields
        (field (name "Manufacturer Part") "0603WAF0000T5E")
        (field (name "Manufacturer") "UNI-ROYAL(厚声)")
      )
      (libsource (lib "easyedapro") (part "0603WAF0000T5E"))
    )
    (comp (ref "R110")
      (value "0Ω")
      (footprint "easyedapro:R0603")
      (fields
        (field (name "Manufacturer Part") "0603WAF0000T5E")
        (field (name "Manufacturer") "UNI-ROYAL(厚声)")
      )
      (libsource (lib "easyedapro") (part "0603WAF0000T5E"))
    )
    (comp (ref "R111")
      (value "0Ω")
      (footprint "easyedapro:R0603")
      (fields
        (field (name "Manufacturer Part") "0603WAF0000T5E")
        (field (name "Manufacturer") "UNI-ROYAL(厚声)")
      )
      (libsource (lib "easyedapro") (part "0603WAF0000T5E"))
    )
    (comp (ref "R112")
      (value "0Ω")
      (footprint "easyedapro:R0603")
      (fields
        (field (name "Manufacturer Part") "0603WAF0000T5E")
        (field (name "Manufacturer") "UNI-ROYAL(厚声)")
      )
      (libsource (lib "easyedapro") (part "0603WAF0000T5E"))
    )
    (comp (ref "R113")
      (value "0Ω")
      (footprint "easyedapro:R0603")
      (fields
        (field (name "Manufacturer Part") "0603WAF0000T5E")
        (field (name "Manufacturer") "UNI-ROYAL(厚声)")
      )
      (libsource (lib "easyedapro") (part "0603WAF0000T5E"))
    )
    (comp (ref "U48")
      (value "HC-PM254-5.0H-2x3PS-02A")
      (footprint "easyedapro:CONN-SMD_HC-PM254-5.0H-2X3PS-02A")
      (fields (field (name "Manufacturer") "HC(虹成电子)"))
      (libsource (lib "easyedapro") (part "HC-PM254-5.0H-2X3PS-02A"))
    )
    (comp (ref "U49")
      (value "HC-PM254-5.0H-2x3PS-02A")
      (footprint "easyedapro:CONN-SMD_HC-PM254-5.0H-2X3PS-02A")
      (fields (field (name "Manufacturer") "HC(虹成电子)"))
      (libsource (lib "easyedapro") (part "HC-PM254-5.0H-2X3PS-02A"))
    )
    (comp (ref "U50")
      (value "HC-PM254-5.0H-2x3PS-02A")
      (footprint "easyedapro:CONN-SMD_HC-PM254-5.0H-2X3PS-02A")
      (fields (field (name "Manufacturer") "HC(虹成电子)"))
      (libsource (lib "easyedapro") (part "HC-PM254-5.0H-2X3PS-02A"))
    )
    (comp (ref "U51")
      (value "HC-PM254-5.0H-2x3PS-02A")
      (footprint "easyedapro:CONN-SMD_HC-PM254-5.0H-2X3PS-02A")
      (fields (field (name "Manufacturer") "HC(虹成电子)"))
      (libsource (lib "easyedapro") (part "HC-PM254-5.0H-2X3PS-02A"))
    )
    (comp (ref "U52")
      (value "HC-PM254-5.0H-2x3PS-02A")
      (footprint "easyedapro:CONN-SMD_HC-PM254-5.0H-2X3PS-02A")
      (fields (field (name "Manufacturer") "HC(虹成电子)"))
      (libsource (lib "easyedapro") (part "HC-PM254-5.0H-2X3PS-02A"))
    )
    (comp (ref "U53")
      (value "HC-PM254-5.0H-2x3PS-02A")
      (footprint "easyedapro:CONN-SMD_HC-PM254-5.0H-2X3PS-02A")
      (fields (field (name "Manufacturer") "HC(虹成电子)"))
      (libsource (lib "easyedapro") (part "HC-PM254-5.0H-2X3PS-02A"))
    )
    (comp (ref "C46")
      (value "10uF")
      (footprint "easyedapro:CAP-TH_BD5.0-P5.00-D1.0-FD")
      (fields
        (field (name "Manufacturer Part") "UVZ1C100MDD1TA")
        (field (name "Manufacturer") "Nichicon(尼吉康)")
      )
      (libsource (lib "easyedapro") (part "UVZ1C100MDD1TA"))
    )
    (comp (ref "C65")
      (value "100nF")
      (footprint "easyedapro:C0603")
      (fields
        (field (name "Manufacturer Part") "CC0603KRX7R6BB104")
        (field (name "Manufacturer") "YAGEO(国巨)")
      )
      (libsource (lib "easyedapro") (part "CC0603KRX7R6BB104"))
    )
    (comp (ref "C84")
      (value "100nF")
      (footprint "easyedapro:C0603")
      (fields
        (field (name "Manufacturer Part") "CC0603KRX7R6BB104")
        (field (name "Manufacturer") "YAGEO(国巨)")
      )
      (libsource (lib "easyedapro") (part "CC0603KRX7R6BB104"))
    )
    (comp (ref "L16")
      (value "LI1206H151R-10")
      (footprint "easyedapro:L1206")
      (description "Impedance @ Frequency:150Ω@100MHz DC Resistance(DCR):150mΩ Number of Circuits:1")
      (fields (field (name "Manufacturer") "Laird(莱尔德)"))
      (libsource (lib "easyedapro") (part "LI1206H151R-10"))
    )
    (comp (ref "L17")
      (value "LI1206H151R-10")
      (footprint "easyedapro:L1206")
      (description "Impedance @ Frequency:150Ω@100MHz DC Resistance(DCR):150mΩ Number of Circuits:1")
      (fields (field (name "Manufacturer") "Laird(莱尔德)"))
      (libsource (lib "easyedapro") (part "LI1206H151R-10"))
    )
    (comp (ref "L18")
      (value "LI1206H151R-10")
      (footprint "easyedapro:L1206")
      (description "Impedance @ Frequency:150Ω@100MHz DC Resistance(DCR):150mΩ Number of Circuits:1")
      (fields (field (name "Manufacturer") "Laird(莱尔德)"))
      (libsource (lib "easyedapro") (part "LI1206H151R-10"))
    )
    (comp (ref "L19")
      (value "LI1206H151R-10")
      (footprint "easyedapro:L1206")
      (description "Impedance @ Frequency:150Ω@100MHz DC Resistance(DCR):150mΩ Number of Circuits:1")
      (fields (field (name "Manufacturer") "Laird(莱尔德)"))
      (libsource (lib "easyedapro") (part "LI1206H151R-10"))
    )
    (comp (ref "L20")
      (value "LI1206H151R-10")
      (footprint "easyedapro:L1206")
      (description "Impedance @ Frequency:150Ω@100MHz DC Resistance(DCR):150mΩ Number of Circuits:1")
      (fields (field (name "Manufacturer") "Laird(莱尔德)"))
      (libsource (lib "easyedapro") (part "LI1206H151R-10"))
    )
    (comp (ref "P1")
      (value "2.54-1*6P")
      (footprint "easyedapro:HDR-TH_6P-P2.54-V-F")
      (fields (field (name "Manufacturer") "BOOMELE(博穆精密)"))
      (libsource (lib "easyedapro") (part "Header-Female-2.54_1x6"))
    )
    (comp (ref "P2")
      (value "2.54-1*6P")
      (footprint "easyedapro:HDR-TH_6P-P2.54-V-F")
      (fields (field (name "Manufacturer") "BOOMELE(博穆精密)"))
      (libsource (lib "easyedapro") (part "Header-Female-2.54_1x6"))
    )
    (comp (ref "U10")
      (value "TB6612FNG,C,8,EL")
      (footprint "easyedapro:SSOP-24_L8.3-W5.6-P0.65-LS7.6-BL")
      (fields (field (name "Manufacturer") "TOSHIBA(东芝)"))
      (libsource (lib "easyedapro") (part "TB6612FNG,C,8,EL"))
    )
    (comp (ref "C100")
      (value "100nF")
      (footprint "easyedapro:C0603")
      (fields
        (field (name "Manufacturer Part") "CC0603KRX7R6BB104")
        (field (name "Manufacturer") "YAGEO(国巨)")
      )
      (libsource (lib "easyedapro") (part "CC0603KRX7R6BB104"))
    )
    (comp (ref "C101")
      (value "10uF")
      (footprint "easyedapro:C0805")
      (description "Capacitance:10uF Tolerance:±10% Tolerance:±10% Voltage Rating:25V Temperature Coefficient:X5R")
      (fields
        (field (name "Manufacturer Part") "CL21A106KAYNNNE")
        (field (name "Manufacturer") "SAMSUNG(三星)")
      )
      (libsource (lib "easyedapro") (part "CL21A106KAYNNNE"))
    )
    (comp (ref "CN2")
      (value "HX-PH2.0-2PZZ")
      (footprint "easyedapro:CONN-TH_2P-P2.50_HX-PH2.0-2PZZ")
      (fields (field (name "Manufacturer") "hanxia(韩下)"))
      (libsource (lib "easyedapro") (part "HX-PH2.0-2PZZ"))
    )
    (comp (ref "CN3")
      (value "HX-PH2.0-2PZZ")
      (footprint "easyedapro:CONN-TH_2P-P2.50_HX-PH2.0-2PZZ")
      (fields (field (name "Manufacturer") "hanxia(韩下)"))
      (libsource (lib "easyedapro") (part "HX-PH2.0-2PZZ"))
    )
    (comp (ref "R114")
      (value "10K")
      (footprint "easyedapro:R0402")
      (description "DNI")
      (libsource (lib "easyedapro") (part "Res"))
    )
    (comp (ref "U55")
      (value "DRV8838DSGR")
      (footprint "easyedapro:WSON-8_L2.0-W2.0-P0.50-TL-EP")
      (fields (field (name "Manufacturer") "TI(德州仪器)"))
      (libsource (lib "easyedapro") (part "DRV8838DSGR"))
    )
  )
  (nets
    (net (code "1") (name "+3V3") (class "Default")
      (node (ref "C100") (pin "2") (pinfunction "2_2") (pintype "input"))
      (node (ref "C43") (pin "1") (pinfunction "1_1") (pintype "input"))
      (node (ref "C95") (pin "2") (pinfunction "2_2") (pintype "input"))
      (node (ref "C96") (pin "2") (pinfunction "2_2") (pintype "input"))
      (node (ref "C97") (pin "2") (pinfunction "2_2") (pintype "input"))
      (node (ref "C98") (pin "2") (pinfunction "2_2") (pintype "input"))
      (node (ref "H1") (pin "1") (pinfunction "1_1") (pintype "input"))
      (node (ref "L14") (pin "2") (pinfunction "2_2") (pintype "unspecified"))
      (node (ref "L20") (pin "2") (pinfunction "2_2") (pintype "unspecified"))
      (node (ref "L22") (pin "2") (pinfunction "2_2") (pintype "unspecified"))
      (node (ref "P1") (pin "3") (pinfunction "3_3") (pintype "input"))
      (node (ref "P2") (pin "3") (pinfunction "3_3") (pintype "input"))
      (node (ref "P4") (pin "1") (pinfunction "1_1") (pintype "unspecified"))
      (node (ref "R105") (pin "2") (pinfunction "2_2") (pintype "input"))
      (node (ref "R114") (pin "2") (pinfunction "2_2") (pintype "input"))
      (node (ref "R52") (pin "2") (pinfunction "2_2") (pintype "input"))
      (node (ref "R53") (pin "2") (pinfunction "2_2") (pintype "input"))
      (node (ref "R54") (pin "2") (pinfunction "2_2") (pintype "input"))
      (node (ref "U1") (pin "1") (pinfunction "VBAT_1") (pintype "unspecified"))
      (node (ref "U1") (pin "13") (pinfunction "VDDA/VREF+_13") (pintype "unspecified"))
      (node (ref "U1") (pin "19") (pinfunction "VDD_19") (pintype "unspecified"))
      (node (ref "U1") (pin "32") (pinfunction "VDD_32") (pintype "unspecified"))
      (node (ref "U1") (pin "48") (pinfunction "VDD_48") (pintype "unspecified"))
      (node (ref "U1") (pin "64") (pinfunction "VDD_64") (pintype "unspecified"))
      (node (ref "U10") (pin "19") (pinfunction "STBY_19") (pintype "unspecified"))
      (node (ref "U47") (pin "1") (pinfunction "1_1") (pintype "unspecified"))
      (node (ref "U48") (pin "6") (pinfunction "6_6") (pintype "unspecified"))
      (node (ref "U49") (pin "6") (pinfunction "6_6") (pintype "unspecified"))
      (node (ref "U50") (pin "6") (pinfunction "6_6") (pintype "unspecified"))
      (node (ref "U51") (pin "6") (pinfunction "6_6") (pintype "unspecified"))
      (node (ref "U52") (pin "6") (pinfunction "6_6") (pintype "unspecified"))
      (node (ref "U53") (pin "6") (pinfunction "6_6") (pintype "unspecified"))
      (node (ref "U55") (pin "8") (pinfunction "VCC_8") (pintype "unspecified"))
    )
    (net (code "2") (name "+6V_MOT") (class "Default")
      (node (ref "C46") (pin "1") (pinfunction "1_1") (pintype "input"))
      (node (ref "C65") (pin "2") (pinfunction "2_2") (pintype "input"))
      (node (ref "L16") (pin "2") (pinfunction "2_2") (pintype "unspecified"))
      (node (ref "L17") (pin "2") (pinfunction "2_2") (pintype "unspecified"))
      (node (ref "U10") (pin "13") (pinfunction "VM2_13") (pintype "unspecified"))
      (node (ref "U10") (pin "14") (pinfunction "VM3_14") (pintype "unspecified"))
      (node (ref "U10") (pin "24") (pinfunction "VM1_24") (pintype "unspecified"))
    )
    (net (code "3") (name "6V") (class "Default")
      (node (ref "C101") (pin "2") (pinfunction "2_2") (pintype "unspecified"))
      (node (ref "L16") (pin "1") (pinfunction "1_1") (pintype "unspecified"))
      (node (ref "L17") (pin "1") (pinfunction "1_1") (pintype "unspecified"))
      (node (ref "R104") (pin "2") (pinfunction "2_2") (pintype "input"))
      (node (ref "R94") (pin "2") (pinfunction "2_2") (pintype "unspecified"))
      (node (ref "U33") (pin "2") (pinfunction "2_2") (pintype "unspecified"))
      (node (ref "U34") (pin "1") (pinfunction "1_1") (pintype "input"))
      (node (ref "U55") (pin "1") (pinfunction "VM_1") (pintype "unspecified"))
    )
    (net (code "4") (name "AGND") (class "Default")
      (node (ref "C46") (pin "2") (pinfunction "2_2") (pintype "input"))
      (node (ref "C65") (pin "1") (pinfunction "1_1") (pintype "input"))
      (node (ref "L18") (pin "2") (pinfunction "2_2") (pintype "unspecified"))
      (node (ref "L19") (pin "2") (pinfunction "2_2") (pintype "unspecified"))
      (node (ref "U10") (pin "10") (pinfunction "PGND2_10") (pintype "unspecified"))
      (node (ref "U10") (pin "3") (pinfunction "PGND1_3") (pintype "unspecified"))
      (node (ref "U10") (pin "4") (pinfunction "PGND1_4") (pintype "unspecified"))
      (node (ref "U10") (pin "9") (pinfunction "PGND2_9") (pintype "unspecified"))
    )
    (net (code "5") (name "BOOT_O") (class "Default")
      (node (ref "R55") (pin "1") (pinfunction "1_1") (pintype "input"))
      (node (ref "U1") (pin "60") (pinfunction "BOOT0_60") (pintype "unspecified"))
    )
    (net (code "6") (name "BTN_02") (class "Default")
      (node (ref "C67") (pin "2") (pinfunction "2_2") (pintype "input"))
      (node (ref "R53") (pin "1") (pinfunction "1_1") (pintype "input"))
      (node (ref "R77") (pin "1") (pinfunction "1_1") (pintype "input"))
      (node (ref "U1") (pin "27") (pinfunction "PB1_27") (pintype "unspecified"))
    )
    (net (code "7") (name "BTN_03") (class "Default")
      (node (ref "C68") (pin "2") (pinfunction "2_2") (pintype "input"))
      (node (ref "R54") (pin "1") (pinfunction "1_1") (pintype "input"))
      (node (ref "R78") (pin "1") (pinfunction "1_1") (pintype "input"))
      (node (ref "U1") (pin "28") (pinfunction "PB2_28") (pintype "unspecified"))
    )
    (net (code "8") (name "ENC_OUT_A1") (class "Default")
      (node (ref "P1") (pin "4") (pinfunction "4_4") (pintype "input"))
      (node (ref "U1") (pin "22") (pinfunction "PA6_22") (pintype "unspecified"))
    )
    (net (code "9") (name "ENC_OUT_A2") (class "Default")
      (node (ref "P2") (pin "4") (pinfunction "4_4") (pintype "input"))
      (node (ref "U1") (pin "41") (pinfunction "PA8_41") (pintype "unspecified"))
    )
    (net (code "10") (name "ENC_OUT_B1") (class "Default")
      (node (ref "P1") (pin "5") (pinfunction "5_5") (pintype "input"))
      (node (ref "U1") (pin "23") (pinfunction "PA7_23") (pintype "unspecified"))
    )
    (net (code "11") (name "ENC_OUT_B2") (class "Default")
      (node (ref "P2") (pin "5") (pinfunction "5_5") (pintype "input"))
      (node (ref "U1") (pin "42") (pinfunction "PA9_42") (pintype "unspecified"))
    )
    (net (code "12") (name "GND") (class "Default")
      (node (ref "C100") (pin "1") (pinfunction "1_1") (pintype "input"))
      (node (ref "C101") (pin "1") (pinfunction "1_1") (pintype "unspecified"))
      (node (ref "C43") (pin "2") (pinfunction "2_2") (pintype "input"))
      (node (ref "C66") (pin "1") (pinfunction "1_1") (pintype "input"))
      (node (ref "C67") (pin "1") (pinfunction "1_1") (pintype "input"))
      (node (ref "C68") (pin "1") (pinfunction "1_1") (pintype "input"))
      (node (ref "C84") (pin "1") (pinfunction "1_1") (pintype "input"))
      (node (ref "C86") (pin "1") (pinfunction "1_1") (pintype "unspecified"))
      (node (ref "C87") (pin "1") (pinfunction "1_1") (pintype "input"))
      (node (ref "C89") (pin "1") (pinfunction "1_1") (pintype "unspecified"))
      (node (ref "C90") (pin "1") (pinfunction "1_1") (pintype "input"))
      (node (ref "C95") (pin "1") (pinfunction "1_1") (pintype "input"))
      (node (ref "C96") (pin "1") (pinfunction "1_1") (pintype "input"))
      (node (ref "C97") (pin "1") (pinfunction "1_1") (pintype "input"))
      (node (ref "C98") (pin "1") (pinfunction "1_1") (pintype "input"))
      (node (ref "C99") (pin "1") (pinfunction "1_1") (pintype "unspecified"))
      (node (ref "CN1") (pin "2") (pinfunction "2_2") (pintype "unspecified"))
      (node (ref "D3") (pin "1") (pinfunction "1_1") (pintype "input"))
      (node (ref "D4") (pin "2") (pinfunction "2_2") (pintype "unspecified"))
      (node (ref "D5") (pin "2") (pinfunction "2_2") (pintype "unspecified"))
      (node (ref "L18") (pin "1") (pinfunction "1_1") (pintype "unspecified"))
      (node (ref "L19") (pin "1") (pinfunction "1_1") (pintype "unspecified"))
      (node (ref "LED15") (pin "2") (pinfunction "K_2") (pintype "unspecified"))
      (node (ref "LED16") (pin "2") (pinfunction "K_2") (pintype "unspecified"))
      (node (ref "LED18") (pin "2") (pinfunction "K_2") (pintype "unspecified"))
      (node (ref "LED7") (pin "2") (pinfunction "K_2") (pintype "unspecified"))
      (node (ref "LED8") (pin "2") (pinfunction "K_2") (pintype "unspecified"))
      (node (ref "P1") (pin "6") (pinfunction "6_6") (pintype "input"))
      (node (ref "P2") (pin "6") (pinfunction "6_6") (pintype "input"))
      (node (ref "P3") (pin "6") (pinfunction "6_6") (pintype "input"))
      (node (ref "P4") (pin "2") (pinfunction "2_2") (pintype "unspecified"))
      (node (ref "P6") (pin "6") (pinfunction "6_6") (pintype "input"))
      (node (ref "R103") (pin "1") (pinfunction "1_1") (pintype "input"))
      (node (ref "R55") (pin "2") (pinfunction "2_2") (pintype "input"))
      (node (ref "R93") (pin "1") (pinfunction "1_1") (pintype "input"))
      (node (ref "R95") (pin "1") (pinfunction "1_1") (pintype "input"))
      (node (ref "R96") (pin "1") (pinfunction "1_1") (pintype "input"))
      (node (ref "SW2") (pin "2") (pinfunction "2_2") (pintype "input"))
      (node (ref "SW3") (pin "2") (pinfunction "2_2") (pintype "input"))
      (node (ref "SW4") (pin "2") (pinfunction "2_2") (pintype "input"))
      (node (ref "U1") (pin "12") (pinfunction "VSSA/VREF-_12") (pintype "unspecified"))
      (node (ref "U1") (pin "18") (pinfunction "VSS_18") (pintype "unspecified"))
      (node (ref "U1") (pin "31") (pinfunction "VSS_31") (pintype "unspecified"))
      (node (ref "U1") (pin "47") (pinfunction "VSS_47") (pintype "unspecified"))
      (node (ref "U1") (pin "63") (pinfunction "VSS_63") (pintype "unspecified"))
      (node (ref "U10") (pin "18") (pinfunction "GND_18") (pintype "unspecified"))
      (node (ref "U30") (pin "3") (pinfunction "INH_3") (pintype "input"))
      (node (ref "U30") (pin "7") (pinfunction "GND_7") (pintype "input"))
      (node (ref "U30") (pin "9") (pinfunction "EP_9") (pintype "input"))
      (node (ref "U34") (pin "2") (pinfunction "2_2") (pintype "input"))
      (node (ref "U35") (pin "3") (pinfunction "INH_3") (pintype "input"))
      (node (ref "U35") (pin "7") (pinfunction "GND_7") (pintype "input"))
      (node (ref "U35") (pin "9") (pinfunction "EP_9") (pintype "input"))
      (node (ref "U37") (pin "2") (pinfunction "2_2") (pintype "input"))
      (node (ref "U47") (pin "5") (pinfunction "5_5") (pintype "unspecified"))
      (node (ref "U48") (pin "5") (pinfunction "5_5") (pintype "unspecified"))
      (node (ref "U49") (pin "5") (pinfunction "5_5") (pintype "unspecified"))
      (node (ref "U50") (pin "5") (pinfunction "5_5") (pintype "unspecified"))
      (node (ref "U51") (pin "5") (pinfunction "5_5") (pintype "unspecified"))
      (node (ref "U52") (pin "5") (pinfunction "5_5") (pintype "unspecified"))
      (node (ref "U53") (pin "5") (pinfunction "5_5") (pintype "unspecified"))
      (node (ref "U55") (pin "4") (pinfunction "GND_4") (pintype "unspecified"))
      (node (ref "U55") (pin "9") (pinfunction "PAD_9") (pintype "unspecified"))
    )
    (net (code "13") (name "GPIO0_IR_LL") (class "Default")
      (node (ref "U1") (pin "11") (pinfunction "PC3_11") (pintype "unspecified"))
      (node (ref "U53") (pin "1") (pinfunction "1_1") (pintype "unspecified"))
    )
    (net (code "14") (name "GPIO0_IR_LM") (class "Default")
      (node (ref "U1") (pin "10") (pinfunction "PC2_10") (pintype "unspecified"))
      (node (ref "U52") (pin "1") (pinfunction "1_1") (pintype "unspecified"))
    )
    (net (code "15") (name "GPIO0_IR_LR") (class "Default")
      (node (ref "U1") (pin "25") (pinfunction "PC5_25") (pintype "unspecified"))
      (node (ref "U51") (pin "1") (pinfunction "1_1") (pintype "unspecified"))
    )
    (net (code "16") (name "GPIO0_IR_RL") (class "Default")
      (node (ref "U1") (pin "24") (pinfunction "PC4_24") (pintype "unspecified"))
      (node (ref "U50") (pin "1") (pinfunction "1_1") (pintype "unspecified"))
    )
    (net (code "17") (name "GPIO0_IR_RM") (class "Default")
      (node (ref "U1") (pin "2") (pinfunction "PC13_2") (pintype "unspecified"))
      (node (ref "U49") (pin "1") (pinfunction "1_1") (pintype "unspecified"))
    )
    (net (code "18") (name "GPIO0_IR_RR") (class "Default")
      (node (ref "U1") (pin "59") (pinfunction "PB7_59") (pintype "unspecified"))
      (node (ref "U48") (pin "1") (pinfunction "1_1") (pintype "unspecified"))
    )
    (net (code "19") (name "GPIO1_IR_LL") (class "Default")
      (node (ref "R113") (pin "1") (pinfunction "1_1") (pintype "input"))
      (node (ref "U53") (pin "2") (pinfunction "2_2") (pintype "unspecified"))
    )
    (net (code "20") (name "GPIO1_IR_LM") (class "Default")
      (node (ref "R112") (pin "1") (pinfunction "1_1") (pintype "input"))
      (node (ref "U52") (pin "2") (pinfunction "2_2") (pintype "unspecified"))
    )
    (net (code "21") (name "GPIO1_IR_LR") (class "Default")
      (node (ref "R111") (pin "1") (pinfunction "1_1") (pintype "input"))
      (node (ref "U51") (pin "2") (pinfunction "2_2") (pintype "unspecified"))
    )
    (net (code "22") (name "GPIO1_IR_RL") (class "Default")
      (node (ref "R110") (pin "1") (pinfunction "1_1") (pintype "input"))
      (node (ref "U50") (pin "2") (pinfunction "2_2") (pintype "unspecified"))
    )
    (net (code "23") (name "GPIO1_IR_RM") (class "Default")
      (node (ref "R109") (pin "1") (pinfunction "1_1") (pintype "input"))
      (node (ref "U49") (pin "2") (pinfunction "2_2") (pintype "unspecified"))
    )
    (net (code "24") (name "GPIO1_IR_RR") (class "Default")
      (node (ref "R108") (pin "1") (pinfunction "1_1") (pintype "input"))
      (node (ref "U48") (pin "2") (pinfunction "2_2") (pintype "unspecified"))
    )
    (net (code "25") (name "I2C2_SCL") (class "Default")
      (node (ref "P4") (pin "3") (pinfunction "3_3") (pintype "unspecified"))
      (node (ref "U1") (pin "29") (pinfunction "PB10_29") (pintype "unspecified"))
      (node (ref "U48") (pin "4") (pinfunction "4_4") (pintype "unspecified"))
      (node (ref "U49") (pin "4") (pinfunction "4_4") (pintype "unspecified"))
      (node (ref "U50") (pin "4") (pinfunction "4_4") (pintype "unspecified"))
      (node (ref "U51") (pin "4") (pinfunction "4_4") (pintype "unspecified"))
      (node (ref "U52") (pin "4") (pinfunction "4_4") (pintype "unspecified"))
      (node (ref "U53") (pin "4") (pinfunction "4_4") (pintype "unspecified"))
    )
    (net (code "26") (name "I2C2_SDA") (class "Default")
      (node (ref "P4") (pin "4") (pinfunction "4_4") (pintype "unspecified"))
      (node (ref "U1") (pin "53") (pinfunction "PC12_53") (pintype "unspecified"))
      (node (ref "U48") (pin "3") (pinfunction "3_3") (pintype "unspecified"))
      (node (ref "U49") (pin "3") (pinfunction "3_3") (pintype "unspecified"))
      (node (ref "U50") (pin "3") (pinfunction "3_3") (pintype "unspecified"))
      (node (ref "U51") (pin "3") (pinfunction "3_3") (pintype "unspecified"))
      (node (ref "U52") (pin "3") (pinfunction "3_3") (pintype "unspecified"))
      (node (ref "U53") (pin "3") (pinfunction "3_3") (pintype "unspecified"))
    )
    (net (code "27") (name "IMU_ADR") (class "Default")
      (node (ref "P4") (pin "5") (pinfunction "5_5") (pintype "unspecified"))
      (node (ref "U1") (pin "35") (pinfunction "PB14_35") (pintype "unspecified"))
    )
    (net (code "28") (name "IMU_BOOT") (class "Default")
      (node (ref "P4") (pin "7") (pinfunction "7_7") (pintype "unspecified"))
      (node (ref "U1") (pin "34") (pinfunction "PB13_34") (pintype "unspecified"))
    )
    (net (code "29") (name "IMU_RESET") (class "Default")
      (node (ref "P4") (pin "8") (pinfunction "8_8") (pintype "unspecified"))
      (node (ref "U1") (pin "33") (pinfunction "PB12_33") (pintype "unspecified"))
    )
    (net (code "30") (name "LIPO+") (class "Default")
      (node (ref "C86") (pin "2") (pinfunction "2_2") (pintype "unspecified"))
      (node (ref "C89") (pin "2") (pinfunction "2_2") (pintype "unspecified"))
      (node (ref "D3") (pin "2") (pinfunction "2_2") (pintype "input"))
      (node (ref "F2") (pin "1") (pinfunction "1_1") (pintype "unspecified"))
      (node (ref "U30") (pin "8") (pinfunction "VCC_8") (pintype "input"))
      (node (ref "U35") (pin "8") (pinfunction "VCC_8") (pintype "input"))
    )
    (net (code "31") (name "M_AIN1") (class "Default")
      (node (ref "U1") (pin "43") (pinfunction "PA10_43") (pintype "unspecified"))
      (node (ref "U10") (pin "21") (pinfunction "AIN1_21") (pintype "unspecified"))
    )
    (net (code "32") (name "M_AIN2") (class "Default")
      (node (ref "U1") (pin "40") (pinfunction "PC9_40") (pintype "unspecified"))
      (node (ref "U10") (pin "22") (pinfunction "AIN2_22") (pintype "unspecified"))
    )
    (net (code "33") (name "M_AO1") (class "Default")
      (node (ref "P1") (pin "1") (pinfunction "1_1") (pintype "input"))
      (node (ref "U10") (pin "1") (pinfunction "AO1_1") (pintype "unspecified"))
      (node (ref "U10") (pin "2") (pinfunction "AO1_2") (pintype "unspecified"))
    )
    (net (code "34") (name "M_AO2") (class "Default")
      (node (ref "P1") (pin "2") (pinfunction "2_2") (pintype "input"))
      (node (ref "U10") (pin "5") (pinfunction "AO2_5") (pintype "unspecified"))
      (node (ref "U10") (pin "6") (pinfunction "AO2_6") (pintype "unspecified"))
    )
    (net (code "35") (name "M_BIN1") (class "Default")
      (node (ref "U1") (pin "57") (pinfunction "PB5_57") (pintype "unspecified"))
      (node (ref "U10") (pin "17") (pinfunction "BIN1_17") (pintype "unspecified"))
    )
    (net (code "36") (name "M_BIN2") (class "Default")
      (node (ref "U1") (pin "39") (pinfunction "PC8_39") (pintype "unspecified"))
      (node (ref "U10") (pin "16") (pinfunction "BIN2_16") (pintype "unspecified"))
    )
    (net (code "37") (name "M_BO1") (class "Default")
      (node (ref "P2") (pin "1") (pinfunction "1_1") (pintype "input"))
      (node (ref "U10") (pin "11") (pinfunction "BO1_11") (pintype "unspecified"))
      (node (ref "U10") (pin "12") (pinfunction "BO1_12") (pintype "unspecified"))
    )
    (net (code "38") (name "M_BO2") (class "Default")
      (node (ref "P2") (pin "2") (pinfunction "2_2") (pintype "input"))
      (node (ref "U10") (pin "7") (pinfunction "BO2_7") (pintype "unspecified"))
      (node (ref "U10") (pin "8") (pinfunction "BO2_8") (pintype "unspecified"))
    )
    (net (code "39") (name "M_PWMA") (class "Default")
      (node (ref "U1") (pin "61") (pinfunction "PB8_61") (pintype "unspecified"))
      (node (ref "U10") (pin "23") (pinfunction "PWMA_23") (pintype "unspecified"))
    )
    (net (code "40") (name "M_PWMB") (class "Default")
      (node (ref "U1") (pin "62") (pinfunction "PB9_62") (pintype "unspecified"))
      (node (ref "U10") (pin "15") (pinfunction "PWMB_15") (pintype "unspecified"))
    )
    (net (code "41") (name "Net-(C88-Pad1)") (class "Default")
      (node (ref "C88") (pin "1") (pinfunction "1_1") (pintype "input"))
      (node (ref "R93") (pin "2") (pinfunction "2_2") (pintype "input"))
    )
    (net (code "42") (name "Net-(C91-Pad1)") (class "Default")
      (node (ref "C91") (pin "1") (pinfunction "1_1") (pintype "input"))
      (node (ref "R96") (pin "2") (pinfunction "2_2") (pintype "input"))
    )
    (net (code "43") (name "Net-(CN1-Pad1)") (class "Default")
      (node (ref "CN1") (pin "1") (pinfunction "1_1") (pintype "unspecified"))
      (node (ref "F2") (pin "2") (pinfunction "2_2") (pintype "unspecified"))
    )
    (net (code "44") (name "Net-(L14-Pad1)") (class "Default")
      (node (ref "L14") (pin "1") (pinfunction "1_1") (pintype "unspecified"))
      (node (ref "L22") (pin "1") (pinfunction "1_1") (pintype "unspecified"))
      (node (ref "R102") (pin "2") (pinfunction "2_2") (pintype "input"))
      (node (ref "U36") (pin "2") (pinfunction "2_2") (pintype "unspecified"))
      (node (ref "U37") (pin "1") (pinfunction "1_1") (pintype "input"))
    )
    (net (code "45") (name "Net-(LED7-A)") (class "Default")
      (node (ref "LED7") (pin "1") (pinfunction "A_1") (pintype "unspecified"))
      (node (ref "R46") (pin "1") (pinfunction "1_1") (pintype "input"))
    )
    (net (code "46") (name "Net-(LED8-A)") (class "Default")
      (node (ref "LED8") (pin "1") (pinfunction "A_1") (pintype "unspecified"))
      (node (ref "R47") (pin "1") (pinfunction "1_1") (pintype "input"))
    )
    (net (code "47") (name "Net-(LED15-A)") (class "Default")
      (node (ref "LED15") (pin "1") (pinfunction "A_1") (pintype "unspecified"))
      (node (ref "R104") (pin "1") (pinfunction "1_1") (pintype "input"))
    )
    (net (code "48") (name "Net-(LED16-A)") (class "Default")
      (node (ref "LED16") (pin "1") (pinfunction "A_1") (pintype "unspecified"))
      (node (ref "R105") (pin "1") (pinfunction "1_1") (pintype "input"))
    )
    (net (code "49") (name "Net-(LED18-A)") (class "Default")
      (node (ref "LED18") (pin "1") (pinfunction "A_1") (pintype "unspecified"))
      (node (ref "R107") (pin "1") (pinfunction "1_1") (pintype "input"))
    )
    (net (code "50") (name "Net-(R76-Pad2)") (class "Default")
      (node (ref "R76") (pin "2") (pinfunction "2_2") (pintype "input"))
      (node (ref "SW4") (pin "3") (pinfunction "3_3") (pintype "input"))
    )
    (net (code "51") (name "Net-(R77-Pad2)") (class "Default")
      (node (ref "R77") (pin "2") (pinfunction "2_2") (pintype "input"))
      (node (ref "SW2") (pin "3") (pinfunction "3_3") (pintype "input"))
    )
    (net (code "52") (name "Net-(R78-Pad2)") (class "Default")
      (node (ref "R78") (pin "2") (pinfunction "2_2") (pintype "input"))
      (node (ref "SW3") (pin "3") (pinfunction "3_3") (pintype "input"))
    )
    (net (code "53") (name "Net-(U1-VCAP_1)") (class "Default")
      (node (ref "C99") (pin "2") (pinfunction "2_2") (pintype "unspecified"))
      (node (ref "U1") (pin "30") (pinfunction "VCAP_1_30") (pintype "unspecified"))
    )
    (net (code "54") (name "Net-(U10-VCC)") (class "Default")
      (node (ref "C84") (pin "2") (pinfunction "2_2") (pintype "input"))
      (node (ref "L20") (pin "1") (pinfunction "1_1") (pintype "unspecified"))
      (node (ref "U10") (pin "20") (pinfunction "VCC_20") (pintype "unspecified"))
    )
    (net (code "55") (name "Net-(U30-COMP)") (class "Default")
      (node (ref "C87") (pin "2") (pinfunction "2_2") (pintype "input"))
      (node (ref "C88") (pin "2") (pinfunction "2_2") (pintype "input"))
      (node (ref "U30") (pin "4") (pinfunction "COMP_4") (pintype "output"))
    )
    (net (code "56") (name "Net-(U30-FB)") (class "Default")
      (node (ref "R94") (pin "1") (pinfunction "1_1") (pintype "unspecified"))
      (node (ref "R95") (pin "2") (pinfunction "2_2") (pintype "input"))
      (node (ref "U30") (pin "5") (pinfunction "FB_5") (pintype "input"))
    )
    (net (code "57") (name "Net-(U30-OUT)") (class "Default")
      (node (ref "D4") (pin "1") (pinfunction "1_1") (pintype "unspecified"))
      (node (ref "U30") (pin "1") (pinfunction "OUT_1") (pintype "input"))
      (node (ref "U33") (pin "1") (pinfunction "1_1") (pintype "unspecified"))
    )
    (net (code "58") (name "Net-(U35-COMP)") (class "Default")
      (node (ref "C90") (pin "2") (pinfunction "2_2") (pintype "input"))
      (node (ref "C91") (pin "2") (pinfunction "2_2") (pintype "input"))
      (node (ref "U35") (pin "4") (pinfunction "COMP_4") (pintype "output"))
    )
    (net (code "59") (name "Net-(U35-FB)") (class "Default")
      (node (ref "R102") (pin "1") (pinfunction "1_1") (pintype "input"))
      (node (ref "R103") (pin "2") (pinfunction "2_2") (pintype "input"))
      (node (ref "U35") (pin "5") (pinfunction "FB_5") (pintype "input"))
    )
    (net (code "60") (name "Net-(U35-OUT)") (class "Default")
      (node (ref "D5") (pin "1") (pinfunction "1_1") (pintype "unspecified"))
      (node (ref "U35") (pin "1") (pinfunction "OUT_1") (pintype "input"))
      (node (ref "U36") (pin "1") (pinfunction "1_1") (pintype "unspecified"))
    )
    (net (code "61") (name "Net-(U55-EN)") (class "Default")
      (node (ref "CN3") (pin "2") (pinfunction "2_2") (pintype "unspecified"))
      (node (ref "U55") (pin "5") (pinfunction "EN_5") (pintype "unspecified"))
    )
    (net (code "62") (name "Net-(U55-OUT1)") (class "Default")
      (node (ref "CN2") (pin "2") (pinfunction "2_2") (pintype "unspecified"))
      (node (ref "U55") (pin "2") (pinfunction "OUT1_2") (pintype "unspecified"))
    )
    (net (code "63") (name "Net-(U55-OUT2)") (class "Default")
      (node (ref "CN2") (pin "1") (pinfunction "1_1") (pintype "unspecified"))
      (node (ref "U55") (pin "3") (pinfunction "OUT2_3") (pintype "unspecified"))
    )
    (net (code "64") (name "Net-(U55-PH)") (class "Default")
      (node (ref "CN3") (pin "1") (pinfunction "1_1") (pintype "unspecified"))
      (node (ref "U55") (pin "6") (pinfunction "PH_6") (pintype "unspecified"))
    )
    (net (code "65") (name "Net-(U55-nSLEEP)") (class "Default")
      (node (ref "R114") (pin "1") (pinfunction "1_1") (pintype "input"))
      (node (ref "U55") (pin "7") (pinfunction "nSLEEP_7") (pintype "unspecified"))
    )
    (net (code "66") (name "PA0") (class "Default")
      (node (ref "P5") (pin "3") (pinfunction "3_3") (pintype "input"))
      (node (ref "R110") (pin "2") (pinfunction "2_2") (pintype "input"))
      (node (ref "U1") (pin "14") (pinfunction "PA0_14") (pintype "unspecified"))
    )
    (net (code "67") (name "PA1") (class "Default")
      (node (ref "P5") (pin "4") (pinfunction "4_4") (pintype "input"))
      (node (ref "R111") (pin "2") (pinfunction "2_2") (pintype "input"))
      (node (ref "U1") (pin "15") (pinfunction "PA1_15") (pintype "unspecified"))
    )
    (net (code "68") (name "PA4") (class "Default")
      (node (ref "P5") (pin "5") (pinfunction "5_5") (pintype "input"))
      (node (ref "R112") (pin "2") (pinfunction "2_2") (pintype "input"))
      (node (ref "U1") (pin "20") (pinfunction "PA4_20") (pintype "unspecified"))
    )
    (net (code "69") (name "PA5") (class "Default")
      (node (ref "P5") (pin "6") (pinfunction "6_6") (pintype "input"))
      (node (ref "R113") (pin "2") (pinfunction "2_2") (pintype "input"))
      (node (ref "U1") (pin "21") (pinfunction "PA5_21") (pintype "unspecified"))
    )
    (net (code "70") (name "PB0") (class "Default")
      (node (ref "P5") (pin "2") (pinfunction "2_2") (pintype "input"))
      (node (ref "R109") (pin "2") (pinfunction "2_2") (pintype "input"))
      (node (ref "U1") (pin "26") (pinfunction "PB0_26") (pintype "unspecified"))
    )
    (net (code "71") (name "PC0") (class "Default")
      (node (ref "P5") (pin "1") (pinfunction "1_1") (pintype "input"))
      (node (ref "R108") (pin "2") (pinfunction "2_2") (pintype "input"))
      (node (ref "U1") (pin "8") (pinfunction "PC0_8") (pintype "unspecified"))
    )
    (net (code "72") (name "SPI3_CS0") (class "Default")
      (node (ref "P6") (pin "3") (pinfunction "3_3") (pintype "input"))
      (node (ref "U1") (pin "36") (pinfunction "PB15_36") (pintype "unspecified"))
    )
    (net (code "73") (name "SPI3_CS1") (class "Default")
      (node (ref "P6") (pin "2") (pinfunction "2_2") (pintype "input"))
      (node (ref "U1") (pin "58") (pinfunction "PB6_58") (pintype "unspecified"))
    )
    (net (code "74") (name "SPI3_MISO") (class "Default")
      (node (ref "P6") (pin "4") (pinfunction "4_4") (pintype "input"))
      (node (ref "U1") (pin "52") (pinfunction "PC11_52") (pintype "unspecified"))
    )
    (net (code "75") (name "SPI3_MOSI") (class "Default")
      (node (ref "P6") (pin "5") (pinfunction "5_5") (pintype "input"))
      (node (ref "U1") (pin "9") (pinfunction "PC1_9") (pintype "unspecified"))
    )
    (net (code "76") (name "SPI3_SCK") (class "Default")
      (node (ref "P6") (pin "1") (pinfunction "1_1") (pintype "input"))
      (node (ref "U1") (pin "51") (pinfunction "PC10_51") (pintype "unspecified"))
    )
    (net (code "77") (name "STLINK_JTDI") (class "Default")
      (node (ref "P3") (pin "3") (pinfunction "3_3") (pintype "input"))
      (node (ref "U1") (pin "50") (pinfunction "PA15_50") (pintype "unspecified"))
    )
    (net (code "78") (name "STLINK_NJTRST") (class "Default")
      (node (ref "P3") (pin "5") (pinfunction "5_5") (pintype "input"))
      (node (ref "U1") (pin "56") (pinfunction "PB4_56") (pintype "unspecified"))
    )
    (net (code "79") (name "STLINK_NRST") (class "Default")
      (node (ref "C66") (pin "2") (pinfunction "2_2") (pintype "input"))
      (node (ref "H1") (pin "4") (pinfunction "4_4") (pintype "input"))
      (node (ref "R52") (pin "1") (pinfunction "1_1") (pintype "input"))
      (node (ref "R76") (pin "1") (pinfunction "1_1") (pintype "input"))
      (node (ref "U1") (pin "7") (pinfunction "NRST_7") (pintype "unspecified"))
      (node (ref "U47") (pin "2") (pinfunction "2_2") (pintype "unspecified"))
    )
    (net (code "80") (name "STLINK_RX") (class "Default")
      (node (ref "H1") (pin "3") (pinfunction "3_3") (pintype "input"))
      (node (ref "U1") (pin "17") (pinfunction "PA3_17") (pintype "unspecified"))
    )
    (net (code "81") (name "STLINK_SWO") (class "Default")
      (node (ref "P3") (pin "4") (pinfunction "4_4") (pintype "input"))
      (node (ref "U1") (pin "55") (pinfunction "PB3_55") (pintype "unspecified"))
    )
    (net (code "82") (name "STLINK_TCK") (class "Default")
      (node (ref "P3") (pin "2") (pinfunction "2_2") (pintype "input"))
      (node (ref "U1") (pin "49") (pinfunction "PA14_49") (pintype "unspecified"))
    )
    (net (code "83") (name "STLINK_TMS") (class "Default")
      (node (ref "P3") (pin "1") (pinfunction "1_1") (pintype "input"))
      (node (ref "U1") (pin "46") (pinfunction "PA13_46") (pintype "unspecified"))
    )
    (net (code "84") (name "STLINK_TX") (class "Default")
      (node (ref "H1") (pin "2") (pinfunction "2_2") (pintype "input"))
      (node (ref "U1") (pin "16") (pinfunction "PA2_16") (pintype "unspecified"))
    )
    (net (code "85") (name "ST_LED1") (class "Default")
      (node (ref "R46") (pin "2") (pinfunction "2_2") (pintype "input"))
      (node (ref "U1") (pin "44") (pinfunction "PA11_44") (pintype "unspecified"))
    )
    (net (code "86") (name "ST_LED2") (class "Default")
      (node (ref "R47") (pin "2") (pinfunction "2_2") (pintype "input"))
      (node (ref "U1") (pin "45") (pinfunction "PA12_45") (pintype "unspecified"))
    )
    (net (code "87") (name "ST_LED3") (class "Default")
      (node (ref "R107") (pin "2") (pinfunction "2_2") (pintype "input"))
      (node (ref "U1") (pin "54") (pinfunction "PD2_54") (pintype "unspecified"))
    )
    (net (code "88") (name "UART_RX") (class "Default")
      (node (ref "U1") (pin "38") (pinfunction "PC7_38") (pintype "unspecified"))
      (node (ref "U47") (pin "4") (pinfunction "4_4") (pintype "unspecified"))
    )
    (net (code "89") (name "UART_TX") (class "Default")
      (node (ref "U1") (pin "37") (pinfunction "PC6_37") (pintype "unspecified"))
      (node (ref "U47") (pin "3") (pinfunction "3_3") (pintype "unspecified"))
    )
    (net (code "90") (name "unconnected-(P4-Pad6)") (class "Default")
      (node (ref "P4") (pin "6") (pinfunction "6_6") (pintype "unspecified+no_connect"))
    )
    (net (code "91") (name "unconnected-(SW2-Pad1)") (class "Default")
      (node (ref "SW2") (pin "1") (pinfunction "1_1") (pintype "input+no_connect"))
    )
    (net (code "92") (name "unconnected-(SW2-Pad4)") (class "Default")
      (node (ref "SW2") (pin "4") (pinfunction "4_4") (pintype "input+no_connect"))
    )
    (net (code "93") (name "unconnected-(SW3-Pad1)") (class "Default")
      (node (ref "SW3") (pin "1") (pinfunction "1_1") (pintype "input+no_connect"))
    )
    (net (code "94") (name "unconnected-(SW3-Pad4)") (class "Default")
      (node (ref "SW3") (pin "4") (pinfunction "4_4") (pintype "input+no_connect"))
    )
    (net (code "95") (name "unconnected-(SW4-Pad1)") (class "Default")
      (node (ref "SW4") (pin "1") (pinfunction "1_1") (pintype "input+no_connect"))
    )
    (net (code "96") (name "unconnected-(SW4-Pad4)") (class "Default")
      (node (ref "SW4") (pin "4") (pinfunction "4_4") (pintype "input+no_connect"))
    )
    (net (code "97") (name "unconnected-(U1-PC14-OSC32_IN-Pad3)") (class "Default")
      (node (ref "U1") (pin "3") (pinfunction "PC14-OSC32_IN_3") (pintype "unspecified+no_connect"))
    )
    (net (code "98") (name "unconnected-(U1-PC15-OSC32_OUT-Pad4)") (class "Default")
      (node (ref "U1") (pin "4") (pinfunction "PC15-OSC32_OUT_4") (pintype "unspecified+no_connect"))
    )
    (net (code "99") (name "unconnected-(U1-PH0-OSC_IN-Pad5)") (class "Default")
      (node (ref "U1") (pin "5") (pinfunction "PH0-OSC_IN_5") (pintype "unspecified+no_connect"))
    )
    (net (code "100") (name "unconnected-(U1-PH1-OSC_OUT-Pad6)") (class "Default")
      (node (ref "U1") (pin "6") (pinfunction "PH1-OSC_OUT_6") (pintype "unspecified+no_connect"))
    )
    (net (code "101") (name "unconnected-(U30-SYNC-Pad2)") (class "Default")
      (node (ref "U30") (pin "2") (pinfunction "SYNC_2") (pintype "input+no_connect"))
    )
    (net (code "102") (name "unconnected-(U30-VREF-Pad6)") (class "Default")
      (node (ref "U30") (pin "6") (pinfunction "VREF_6") (pintype "input+no_connect"))
    )
    (net (code "103") (name "unconnected-(U35-SYNC-Pad2)") (class "Default")
      (node (ref "U35") (pin "2") (pinfunction "SYNC_2") (pintype "input+no_connect"))
    )
    (net (code "104") (name "unconnected-(U35-VREF-Pad6)") (class "Default")
      (node (ref "U35") (pin "6") (pinfunction "VREF_6") (pintype "input+no_connect"))
    )
  )
)
